# BMS029B_FETs.net
KiCad netlist of a schematic drawn in Altium Designer
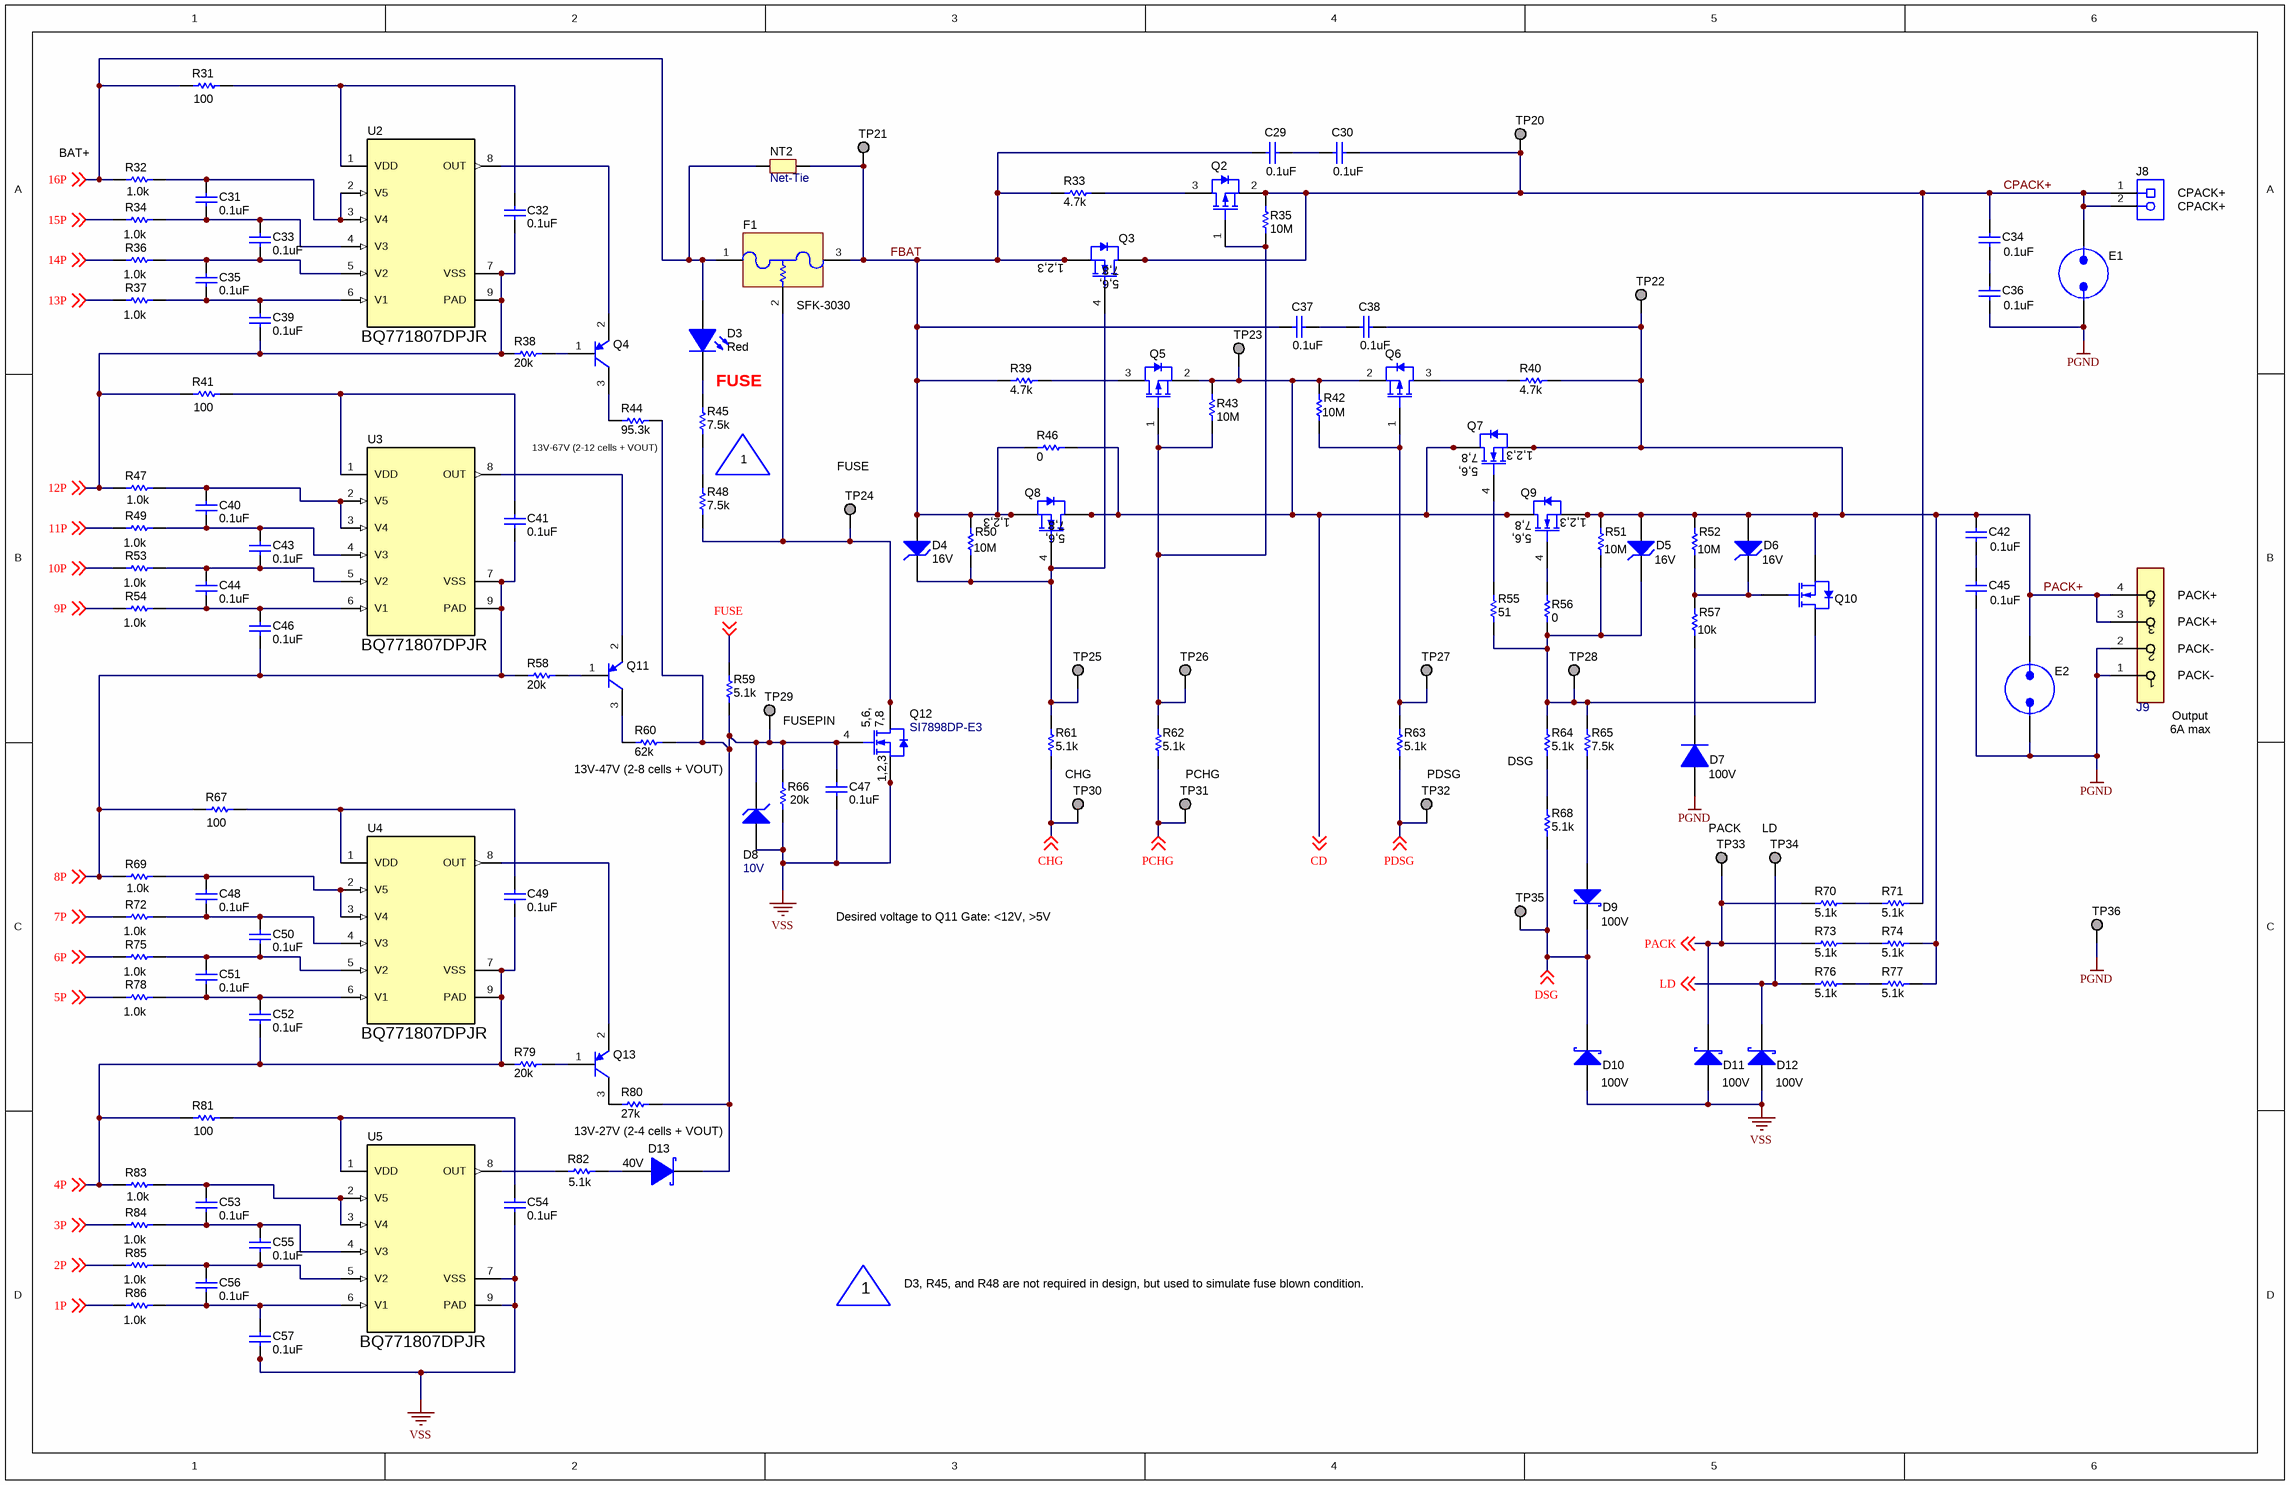
[diagram p0: BMS029B_FETs.SchDoc]

(export (version "E")
  (design (tool "Eeschema 10.0.6"))
  (components
    (comp (ref "C29")
      (value "GCJ188R72A104KA01D")
      (footprint "0603")
      (description "CAP, CERM, 0.1 uF, 100 V,+/- 10%, X7R, AEC-Q200 Grade 1, 0603")
      (fields
        (field (name "MANUFACTURER") "MuRata")
        (field (name "VALUEDISPLAYED") "0.1uF")
        (field (name "PUBLISHER") "Texas Instruments")
      )
      (libsource (lib "Altium Vault - TI") (part "Capacitor"))
    )
    (comp (ref "C30")
      (value "GCJ188R72A104KA01D")
      (footprint "0603")
      (description "CAP, CERM, 0.1 uF, 100 V,+/- 10%, X7R, AEC-Q200 Grade 1, 0603")
      (fields
        (field (name "MANUFACTURER") "MuRata")
        (field (name "VALUEDISPLAYED") "0.1uF")
        (field (name "PUBLISHER") "Texas Instruments")
      )
      (libsource (lib "Altium Vault - TI") (part "Capacitor"))
    )
    (comp (ref "C31")
      (value "885012206095")
      (footprint "0603")
      (description "CAP, CERM, 0.1 uF, 50 V, +/- 10%, X7R, 0603")
      (fields
        (field (name "VALUEDISPLAYED") "0.1uF")
        (field (name "MANUFACTURER") "Wurth Elektronik")
        (field (name "PUBLISHER") "Texas Instruments")
      )
      (libsource (lib "Altium Vault - TI") (part "Capacitor"))
    )
    (comp (ref "C32")
      (value "885012206095")
      (footprint "0603")
      (description "CAP, CERM, 0.1 uF, 50 V, +/- 10%, X7R, 0603")
      (fields
        (field (name "VALUEDISPLAYED") "0.1uF")
        (field (name "MANUFACTURER") "Wurth Elektronik")
        (field (name "PUBLISHER") "Texas Instruments")
      )
      (libsource (lib "Altium Vault - TI") (part "Capacitor"))
    )
    (comp (ref "C33")
      (value "885012206095")
      (footprint "0603")
      (description "CAP, CERM, 0.1 uF, 50 V, +/- 10%, X7R, 0603")
      (fields
        (field (name "VALUEDISPLAYED") "0.1uF")
        (field (name "MANUFACTURER") "Wurth Elektronik")
        (field (name "PUBLISHER") "Texas Instruments")
      )
      (libsource (lib "Altium Vault - TI") (part "Capacitor"))
    )
    (comp (ref "C34")
      (value "GCJ188R72A104KA01D")
      (footprint "0603")
      (description "CAP, CERM, 0.1 uF, 100 V,+/- 10%, X7R, AEC-Q200 Grade 1, 0603")
      (fields
        (field (name "MANUFACTURER") "MuRata")
        (field (name "VALUEDISPLAYED") "0.1uF")
        (field (name "PUBLISHER") "Texas Instruments")
      )
      (libsource (lib "Altium Vault - TI") (part "Capacitor"))
    )
    (comp (ref "C35")
      (value "885012206095")
      (footprint "0603")
      (description "CAP, CERM, 0.1 uF, 50 V, +/- 10%, X7R, 0603")
      (fields
        (field (name "VALUEDISPLAYED") "0.1uF")
        (field (name "MANUFACTURER") "Wurth Elektronik")
        (field (name "PUBLISHER") "Texas Instruments")
      )
      (libsource (lib "Altium Vault - TI") (part "Capacitor"))
    )
    (comp (ref "C36")
      (value "GCJ188R72A104KA01D")
      (footprint "0603")
      (description "CAP, CERM, 0.1 uF, 100 V,+/- 10%, X7R, AEC-Q200 Grade 1, 0603")
      (fields
        (field (name "MANUFACTURER") "MuRata")
        (field (name "VALUEDISPLAYED") "0.1uF")
        (field (name "PUBLISHER") "Texas Instruments")
      )
      (libsource (lib "Altium Vault - TI") (part "Capacitor"))
    )
    (comp (ref "C37")
      (value "GCJ188R72A104KA01D")
      (footprint "0603")
      (description "CAP, CERM, 0.1 uF, 100 V,+/- 10%, X7R, AEC-Q200 Grade 1, 0603")
      (fields
        (field (name "MANUFACTURER") "MuRata")
        (field (name "VALUEDISPLAYED") "0.1uF")
        (field (name "PUBLISHER") "Texas Instruments")
      )
      (libsource (lib "Altium Vault - TI") (part "Capacitor"))
    )
    (comp (ref "C38")
      (value "GCJ188R72A104KA01D")
      (footprint "0603")
      (description "CAP, CERM, 0.1 uF, 100 V,+/- 10%, X7R, AEC-Q200 Grade 1, 0603")
      (fields
        (field (name "MANUFACTURER") "MuRata")
        (field (name "VALUEDISPLAYED") "0.1uF")
        (field (name "PUBLISHER") "Texas Instruments")
      )
      (libsource (lib "Altium Vault - TI") (part "Capacitor"))
    )
    (comp (ref "C39")
      (value "885012206095")
      (footprint "0603")
      (description "CAP, CERM, 0.1 uF, 50 V, +/- 10%, X7R, 0603")
      (fields
        (field (name "VALUEDISPLAYED") "0.1uF")
        (field (name "MANUFACTURER") "Wurth Elektronik")
        (field (name "PUBLISHER") "Texas Instruments")
      )
      (libsource (lib "Altium Vault - TI") (part "Capacitor"))
    )
    (comp (ref "C40")
      (value "885012206095")
      (footprint "0603")
      (description "CAP, CERM, 0.1 uF, 50 V, +/- 10%, X7R, 0603")
      (fields
        (field (name "VALUEDISPLAYED") "0.1uF")
        (field (name "MANUFACTURER") "Wurth Elektronik")
        (field (name "PUBLISHER") "Texas Instruments")
      )
      (libsource (lib "Altium Vault - TI") (part "Capacitor"))
    )
    (comp (ref "C41")
      (value "885012206095")
      (footprint "0603")
      (description "CAP, CERM, 0.1 uF, 50 V, +/- 10%, X7R, 0603")
      (fields
        (field (name "VALUEDISPLAYED") "0.1uF")
        (field (name "MANUFACTURER") "Wurth Elektronik")
        (field (name "PUBLISHER") "Texas Instruments")
      )
      (libsource (lib "Altium Vault - TI") (part "Capacitor"))
    )
    (comp (ref "C42")
      (value "GCJ188R72A104KA01D")
      (footprint "0603")
      (description "CAP, CERM, 0.1 uF, 100 V,+/- 10%, X7R, AEC-Q200 Grade 1, 0603")
      (fields
        (field (name "MANUFACTURER") "MuRata")
        (field (name "VALUEDISPLAYED") "0.1uF")
        (field (name "PUBLISHER") "Texas Instruments")
      )
      (libsource (lib "Altium Vault - TI") (part "Capacitor"))
    )
    (comp (ref "C43")
      (value "885012206095")
      (footprint "0603")
      (description "CAP, CERM, 0.1 uF, 50 V, +/- 10%, X7R, 0603")
      (fields
        (field (name "VALUEDISPLAYED") "0.1uF")
        (field (name "MANUFACTURER") "Wurth Elektronik")
        (field (name "PUBLISHER") "Texas Instruments")
      )
      (libsource (lib "Altium Vault - TI") (part "Capacitor"))
    )
    (comp (ref "C44")
      (value "885012206095")
      (footprint "0603")
      (description "CAP, CERM, 0.1 uF, 50 V, +/- 10%, X7R, 0603")
      (fields
        (field (name "VALUEDISPLAYED") "0.1uF")
        (field (name "MANUFACTURER") "Wurth Elektronik")
        (field (name "PUBLISHER") "Texas Instruments")
      )
      (libsource (lib "Altium Vault - TI") (part "Capacitor"))
    )
    (comp (ref "C45")
      (value "GCJ188R72A104KA01D")
      (footprint "0603")
      (description "CAP, CERM, 0.1 uF, 100 V,+/- 10%, X7R, AEC-Q200 Grade 1, 0603")
      (fields
        (field (name "MANUFACTURER") "MuRata")
        (field (name "VALUEDISPLAYED") "0.1uF")
        (field (name "PUBLISHER") "Texas Instruments")
      )
      (libsource (lib "Altium Vault - TI") (part "Capacitor"))
    )
    (comp (ref "C46")
      (value "885012206095")
      (footprint "0603")
      (description "CAP, CERM, 0.1 uF, 50 V, +/- 10%, X7R, 0603")
      (fields
        (field (name "VALUEDISPLAYED") "0.1uF")
        (field (name "MANUFACTURER") "Wurth Elektronik")
        (field (name "PUBLISHER") "Texas Instruments")
      )
      (libsource (lib "Altium Vault - TI") (part "Capacitor"))
    )
    (comp (ref "C47")
      (value "885012206095")
      (footprint "0603")
      (description "CAP, CERM, 0.1 uF, 50 V, +/- 10%, X7R, 0603")
      (fields
        (field (name "VALUEDISPLAYED") "0.1uF")
        (field (name "MANUFACTURER") "Wurth Elektronik")
        (field (name "PUBLISHER") "Texas Instruments")
      )
      (libsource (lib "Altium Vault - TI") (part "Capacitor"))
    )
    (comp (ref "C48")
      (value "885012206095")
      (footprint "0603")
      (description "CAP, CERM, 0.1 uF, 50 V, +/- 10%, X7R, 0603")
      (fields
        (field (name "VALUEDISPLAYED") "0.1uF")
        (field (name "MANUFACTURER") "Wurth Elektronik")
        (field (name "PUBLISHER") "Texas Instruments")
      )
      (libsource (lib "Altium Vault - TI") (part "Capacitor"))
    )
    (comp (ref "C49")
      (value "885012206095")
      (footprint "0603")
      (description "CAP, CERM, 0.1 uF, 50 V, +/- 10%, X7R, 0603")
      (fields
        (field (name "VALUEDISPLAYED") "0.1uF")
        (field (name "MANUFACTURER") "Wurth Elektronik")
        (field (name "PUBLISHER") "Texas Instruments")
      )
      (libsource (lib "Altium Vault - TI") (part "Capacitor"))
    )
    (comp (ref "C50")
      (value "885012206095")
      (footprint "0603")
      (description "CAP, CERM, 0.1 uF, 50 V, +/- 10%, X7R, 0603")
      (fields
        (field (name "VALUEDISPLAYED") "0.1uF")
        (field (name "MANUFACTURER") "Wurth Elektronik")
        (field (name "PUBLISHER") "Texas Instruments")
      )
      (libsource (lib "Altium Vault - TI") (part "Capacitor"))
    )
    (comp (ref "C51")
      (value "885012206095")
      (footprint "0603")
      (description "CAP, CERM, 0.1 uF, 50 V, +/- 10%, X7R, 0603")
      (fields
        (field (name "VALUEDISPLAYED") "0.1uF")
        (field (name "MANUFACTURER") "Wurth Elektronik")
        (field (name "PUBLISHER") "Texas Instruments")
      )
      (libsource (lib "Altium Vault - TI") (part "Capacitor"))
    )
    (comp (ref "C52")
      (value "885012206095")
      (footprint "0603")
      (description "CAP, CERM, 0.1 uF, 50 V, +/- 10%, X7R, 0603")
      (fields
        (field (name "VALUEDISPLAYED") "0.1uF")
        (field (name "MANUFACTURER") "Wurth Elektronik")
        (field (name "PUBLISHER") "Texas Instruments")
      )
      (libsource (lib "Altium Vault - TI") (part "Capacitor"))
    )
    (comp (ref "C53")
      (value "885012206095")
      (footprint "0603")
      (description "CAP, CERM, 0.1 uF, 50 V, +/- 10%, X7R, 0603")
      (fields
        (field (name "VALUEDISPLAYED") "0.1uF")
        (field (name "MANUFACTURER") "Wurth Elektronik")
        (field (name "PUBLISHER") "Texas Instruments")
      )
      (libsource (lib "Altium Vault - TI") (part "Capacitor"))
    )
    (comp (ref "C54")
      (value "885012206095")
      (footprint "0603")
      (description "CAP, CERM, 0.1 uF, 50 V, +/- 10%, X7R, 0603")
      (fields
        (field (name "VALUEDISPLAYED") "0.1uF")
        (field (name "MANUFACTURER") "Wurth Elektronik")
        (field (name "PUBLISHER") "Texas Instruments")
      )
      (libsource (lib "Altium Vault - TI") (part "Capacitor"))
    )
    (comp (ref "C55")
      (value "885012206095")
      (footprint "0603")
      (description "CAP, CERM, 0.1 uF, 50 V, +/- 10%, X7R, 0603")
      (fields
        (field (name "VALUEDISPLAYED") "0.1uF")
        (field (name "MANUFACTURER") "Wurth Elektronik")
        (field (name "PUBLISHER") "Texas Instruments")
      )
      (libsource (lib "Altium Vault - TI") (part "Capacitor"))
    )
    (comp (ref "C56")
      (value "885012206095")
      (footprint "0603")
      (description "CAP, CERM, 0.1 uF, 50 V, +/- 10%, X7R, 0603")
      (fields
        (field (name "VALUEDISPLAYED") "0.1uF")
        (field (name "MANUFACTURER") "Wurth Elektronik")
        (field (name "PUBLISHER") "Texas Instruments")
      )
      (libsource (lib "Altium Vault - TI") (part "Capacitor"))
    )
    (comp (ref "C57")
      (value "885012206095")
      (footprint "0603")
      (description "CAP, CERM, 0.1 uF, 50 V, +/- 10%, X7R, 0603")
      (fields
        (field (name "VALUEDISPLAYED") "0.1uF")
        (field (name "MANUFACTURER") "Wurth Elektronik")
        (field (name "PUBLISHER") "Texas Instruments")
      )
      (libsource (lib "Altium Vault - TI") (part "Capacitor"))
    )
    (comp (ref "D3")
      (value "Red")
      (footprint "WL-SMCW_RED")
      (description "LED, Red, SMD")
      (fields (field (name "MANUFACTURER") "Wurth Elektronik") (field (name "PARTNUMBER") "150060RS75000"))
      (libsource (lib "Altium Vault - TI") (part "CMP-0002947-3"))
    )
    (comp (ref "D4")
      (value "16V")
      (footprint "SOD-123")
      (description "Diode, Zener, 16 V, 500 mW, SOD-123")
      (fields (field (name "MANUFACTURER") "Diodes Inc.") (field (name "PARTNUMBER") "MMSZ5246B-7-F"))
      (libsource (lib "Altium Vault - TI") (part "Zener"))
    )
    (comp (ref "D5")
      (value "16V")
      (footprint "SOD-123")
      (description "Diode, Zener, 16 V, 500 mW, SOD-123")
      (fields (field (name "PARTNUMBER") "MMSZ5246B-7-F") (field (name "MANUFACTURER") "Diodes Inc."))
      (libsource (lib "Altium Vault - TI") (part "CMP-0005754-4"))
    )
    (comp (ref "D6")
      (value "16V")
      (footprint "SOD-123")
      (description "Diode, Zener, 16 V, 500 mW, SOD-123")
      (fields (field (name "PARTNUMBER") "MMSZ5246B-7-F") (field (name "MANUFACTURER") "Diodes Inc."))
      (libsource (lib "Altium Vault - TI") (part "CMP-0005754-4"))
    )
    (comp (ref "D7")
      (value "100V")
      (footprint "SOD-123")
      (description "Diode, Ultrafast, 100 V, 0.15 A, SOD-123")
      (fields (field (name "PARTNUMBER") "1N4148W-7-F") (field (name "MANUFACTURER") "Diodes Inc."))
      (libsource (lib "Altium Vault - TI") (part "CMP-0029001-2"))
    )
    (comp (ref "D8")
      (value "10V")
      (footprint "SOD-123")
      (description "Diode, Zener, 10 V, 500 mW, SOD-123")
      (fields (field (name "MANUFACTURER") "ON Semiconductor") (field (name "PARTNUMBER") "MMSZ4697T1G"))
      (libsource (lib "Altium Vault - TI") (part "Zener"))
    )
    (comp (ref "D9")
      (value "100V")
      (footprint "SOD-123")
      (description "Diode, Schottky, 100 V, 0.15 A, SOD-123")
      (fields (field (name "MANUFACTURER") "Diodes Inc.") (field (name "PARTNUMBER") "BAT46W-7-F"))
      (libsource (lib "Altium Vault - TI") (part "DIODE_SCHOTTKY"))
    )
    (comp (ref "D10")
      (value "100V")
      (footprint "SOD-123")
      (description "Diode, Schottky, 100 V, 0.15 A, SOD-123")
      (fields (field (name "MANUFACTURER") "Diodes Inc.") (field (name "PARTNUMBER") "BAT46W-7-F"))
      (libsource (lib "Altium Vault - TI") (part "DIODE_SCHOTTKY"))
    )
    (comp (ref "D11")
      (value "100V")
      (footprint "SOD-123")
      (description "Diode, Schottky, 100 V, 0.15 A, SOD-123")
      (fields (field (name "MANUFACTURER") "Diodes Inc.") (field (name "PARTNUMBER") "BAT46W-7-F"))
      (libsource (lib "Altium Vault - TI") (part "DIODE_SCHOTTKY"))
    )
    (comp (ref "D12")
      (value "100V")
      (footprint "SOD-123")
      (description "Diode, Schottky, 100 V, 0.15 A, SOD-123")
      (fields (field (name "MANUFACTURER") "Diodes Inc.") (field (name "PARTNUMBER") "BAT46W-7-F"))
      (libsource (lib "Altium Vault - TI") (part "DIODE_SCHOTTKY"))
    )
    (comp (ref "D13")
      (value "40V")
      (footprint "SOT-323")
      (description "Diode, Schottky, 40 V, 0.2 A, SOT-323")
      (fields (field (name "PARTNUMBER") "BAS40W-7-F") (field (name "MANUFACTURER") "Diodes Inc."))
      (libsource (lib "Altium Vault - TI") (part "CMP-0028438-2"))
    )
    (comp (ref "E1")
      (value "Spark Gap")
      (footprint "SPARK_GAP2")
      (libsource (lib "Altium Vault - TI") (part "CMP-0079939-1"))
    )
    (comp (ref "E2")
      (value "Spark Gap")
      (footprint "SPARK_GAP2")
      (libsource (lib "Altium Vault - TI") (part "CMP-0079939-1"))
    )
    (comp (ref "F1")
      (value "SFK-3030")
      (footprint "FUSE_SFK-xx30x")
      (description "Fuse, 30 A, 62 VDC, SMD")
      (fields (field (name "MANUFACTURER") "Dexerials Corporation"))
      (libsource (lib "Altium Vault - TI") (part "FUSE_SFK-XX30X"))
    )
    (comp (ref "J8")
      (value "ED555/2DS")
      (footprint "TERM_BLK_ED555-2DS")
      (description "Terminal Block, 3.5mm Pitch, 2x1, TH")
      (fields
        (field (name "MANUFACTURER") "On-Shore Technology")
        (field (name "PUBLISHER") "Texas Instruments")
      )
      (libsource (lib "Altium Vault - TI") (part "CMP-0074913-1"))
    )
    (comp (ref "J9")
      (value "OSTTE040161")
      (footprint "FP-OSTTE040161_HDR4-MFG")
      (description "TERM BLOCK 3.5MM VERT 4POS PCB")
      (fields (field (name "MANUFACTURER") "On Shore Technology"))
      (libsource (lib "Altium Vault - TI") (part "SYM-OSTTE040161"))
    )
    (comp (ref "NT2")
      (value "Net-Tie")
      (footprint "Net-Tie_50milWide_30milLong")
      (description "Single point connection between nets.")
      (libsource (lib "Altium Vault - TI") (part "Net-Tie"))
    )
    (comp (ref "Q2")
      (value "SI2325DS-T1-E3")
      (footprint "SOT-23")
      (description "MOSFET, P-CH, -150 V, -0.53 A, SOT-23")
      (fields (field (name "MANUFACTURER") "Vishay-Siliconix"))
      (libsource (lib "Altium Vault - TI") (part "MOSFET_P_D3G1S2"))
    )
    (comp (ref "Q3")
      (value "BSZ900N15NS3 G")
      (footprint "PG-TSDSON-8")
      (description "MOSFET, N-CH, 150 V, 13 A, PG-TSDSON-8")
      (fields
        (field (name "MANUFACTURER") "Infineon Technologies")
        (field (name "PUBLISHER") "Texas Instruments")
      )
      (libsource (lib "Altium Vault - TI") (part "MOSFET_N_D56789G4S123"))
    )
    (comp (ref "Q4")
      (value "MMBT5401LT1G")
      (footprint "SOT-23")
      (description "Transistor, PNP, 150 V, 0.5 A, SOT-23")
      (fields (field (name "MANUFACTURER") "ON Semiconductor") (field (name "PUBLISHER") "Texas Instruments"))
      (libsource (lib "Altium Vault - TI") (part "BJT_PNP_C3B1E2"))
    )
    (comp (ref "Q5")
      (value "SI2325DS-T1-E3")
      (footprint "SOT-23")
      (description "MOSFET, P-CH, -150 V, -0.53 A, SOT-23")
      (fields (field (name "MANUFACTURER") "Vishay-Siliconix"))
      (libsource (lib "Altium Vault - TI") (part "MOSFET_P_D3G1S2"))
    )
    (comp (ref "Q6")
      (value "SI2325DS-T1-E3")
      (footprint "SOT-23")
      (description "MOSFET, P-CH, -150 V, -0.53 A, SOT-23")
      (fields (field (name "MANUFACTURER") "Vishay-Siliconix"))
      (libsource (lib "Altium Vault - TI") (part "MOSFET_P_D3G1S2"))
    )
    (comp (ref "Q7")
      (value "BSC160N15NS5ATMA1")
      (footprint "PG-TDSON-8")
      (description "MOSFET, N-CH, 150 V, 56 A, PG-TDSON-8")
      (fields
        (field (name "MANUFACTURER") "Infineon Technologies")
        (field (name "PUBLISHER") "Texas Instruments")
      )
      (libsource (lib "Altium Vault - TI") (part "MOSFET_N_D56789G4S123"))
    )
    (comp (ref "Q8")
      (value "BSC160N15NS5ATMA1")
      (footprint "PG-TDSON-8")
      (description "MOSFET, N-CH, 150 V, 56 A, PG-TDSON-8")
      (fields
        (field (name "MANUFACTURER") "Infineon Technologies")
        (field (name "PUBLISHER") "Texas Instruments")
      )
      (libsource (lib "Altium Vault - TI") (part "MOSFET_N_D56789G4S123"))
    )
    (comp (ref "Q9")
      (value "BSC160N15NS5ATMA1")
      (footprint "PG-TDSON-8")
      (description "MOSFET, N-CH, 150 V, 56 A, PG-TDSON-8")
      (fields
        (field (name "MANUFACTURER") "Infineon Technologies")
        (field (name "PUBLISHER") "Texas Instruments")
      )
      (libsource (lib "Altium Vault - TI") (part "MOSFET_N_D56789G4S123"))
    )
    (comp (ref "Q10")
      (value "MOSFET_N_D3G1S2")
      (footprint "SOT-323")
      (description "MOSFET, N-CH, 60 V, 0.31 A, SOT-323")
      (fields
        (field (name "PARTNUMBER") "2N7002KW")
        (field (name "MANUFACTURER") "Fairchild Semiconductor")
        (field (name "PUBLISHER") "Texas Instruments")
      )
      (libsource (lib "Altium Vault - TI") (part "CMP-0000774-1"))
    )
    (comp (ref "Q11")
      (value "MMBT5401LT1G")
      (footprint "SOT-23")
      (description "Transistor, PNP, 150 V, 0.5 A, SOT-23")
      (fields (field (name "MANUFACTURER") "ON Semiconductor") (field (name "PUBLISHER") "Texas Instruments"))
      (libsource (lib "Altium Vault - TI") (part "BJT_PNP_C3B1E2"))
    )
    (comp (ref "Q12")
      (value "SI7898DP-E3")
      (footprint "PowerPAK_SO-8")
      (description "MOSFET, N-CH, 150 V, 3 A, PowerPAK SO-8")
      (fields (field (name "MANUFACTURER") "Vishay-Siliconix") (field (name "PUBLISHER") "Texas Instruments"))
      (libsource (lib "Altium Vault - TI") (part "MOSFET_N_D56789G4S123"))
    )
    (comp (ref "Q13")
      (value "MMBT5401LT1G")
      (footprint "SOT-23")
      (description "Transistor, PNP, 150 V, 0.5 A, SOT-23")
      (fields (field (name "MANUFACTURER") "ON Semiconductor") (field (name "PUBLISHER") "Texas Instruments"))
      (libsource (lib "Altium Vault - TI") (part "BJT_PNP_C3B1E2"))
    )
    (comp (ref "R31")
      (value "Resistor")
      (footprint "0603")
      (description "RES, 100, 5%, 0.1 W, AEC-Q200 Grade 0, 0603")
      (fields
        (field (name "PARTNUMBER") "CRCW0603100RJNEA")
        (field (name "MANUFACTURER") "Vishay-Dale")
        (field (name "VALUEDISPLAYED") "100")
        (field (name "PUBLISHER") "Texas Instruments")
      )
      (libsource (lib "Altium Vault - TI") (part "Resistor"))
    )
    (comp (ref "R32")
      (value "Resistor")
      (footprint "0603")
      (description "RES, 1.0 k, 5%, 0.1 W, AEC-Q200 Grade 0, 0603")
      (fields
        (field (name "PARTNUMBER") "CRCW06031K00JNEA")
        (field (name "MANUFACTURER") "Vishay-Dale")
        (field (name "VALUEDISPLAYED") "1.0k")
        (field (name "PUBLISHER") "Texas Instruments")
      )
      (libsource (lib "Altium Vault - TI") (part "Resistor"))
    )
    (comp (ref "R33")
      (value "CRCW25124K70JNEG")
      (footprint "2512")
      (description "RES, 4.7 k, 5%, 1 W, AEC-Q200 Grade 0, 2512")
      (fields (field (name "MANUFACTURER") "Vishay-Dale") (field (name "VALUEDISPLAYED") "4.7k"))
      (libsource (lib "Altium Vault - TI") (part "Resistor"))
    )
    (comp (ref "R34")
      (value "Resistor")
      (footprint "0603")
      (description "RES, 1.0 k, 5%, 0.1 W, AEC-Q200 Grade 0, 0603")
      (fields
        (field (name "PARTNUMBER") "CRCW06031K00JNEA")
        (field (name "MANUFACTURER") "Vishay-Dale")
        (field (name "VALUEDISPLAYED") "1.0k")
        (field (name "PUBLISHER") "Texas Instruments")
      )
      (libsource (lib "Altium Vault - TI") (part "Resistor"))
    )
    (comp (ref "R35")
      (value "Resistor")
      (footprint "0603")
      (description "RES, 10 M, 5%, 0.1 W, AEC-Q200 Grade 0, 0603")
      (fields
        (field (name "PARTNUMBER") "CRCW060310M0JNEA")
        (field (name "MANUFACTURER") "Vishay-Dale")
        (field (name "VALUEDISPLAYED") "10M")
        (field (name "PUBLISHER") "Texas Instruments")
      )
      (libsource (lib "Altium Vault - TI") (part "Resistor"))
    )
    (comp (ref "R36")
      (value "Resistor")
      (footprint "0603")
      (description "RES, 1.0 k, 5%, 0.1 W, AEC-Q200 Grade 0, 0603")
      (fields
        (field (name "PARTNUMBER") "CRCW06031K00JNEA")
        (field (name "MANUFACTURER") "Vishay-Dale")
        (field (name "VALUEDISPLAYED") "1.0k")
        (field (name "PUBLISHER") "Texas Instruments")
      )
      (libsource (lib "Altium Vault - TI") (part "Resistor"))
    )
    (comp (ref "R37")
      (value "Resistor")
      (footprint "0603")
      (description "RES, 1.0 k, 5%, 0.1 W, AEC-Q200 Grade 0, 0603")
      (fields
        (field (name "PARTNUMBER") "CRCW06031K00JNEA")
        (field (name "MANUFACTURER") "Vishay-Dale")
        (field (name "VALUEDISPLAYED") "1.0k")
        (field (name "PUBLISHER") "Texas Instruments")
      )
      (libsource (lib "Altium Vault - TI") (part "Resistor"))
    )
    (comp (ref "R38")
      (value "CRCW060320K0JNEA")
      (footprint "0603")
      (description "RES, 20 k, 5%, 0.1 W, AEC-Q200 Grade 0, 0603")
      (fields (field (name "MANUFACTURER") "Vishay-Dale") (field (name "VALUEDISPLAYED") "20k"))
      (libsource (lib "Altium Vault - TI") (part "Resistor"))
    )
    (comp (ref "R39")
      (value "CRCW25124K70JNEG")
      (footprint "2512")
      (description "RES, 4.7 k, 5%, 1 W, AEC-Q200 Grade 0, 2512")
      (fields (field (name "MANUFACTURER") "Vishay-Dale") (field (name "VALUEDISPLAYED") "4.7k"))
      (libsource (lib "Altium Vault - TI") (part "Resistor"))
    )
    (comp (ref "R40")
      (value "CRCW25124K70JNEG")
      (footprint "2512")
      (description "RES, 4.7 k, 5%, 1 W, AEC-Q200 Grade 0, 2512")
      (fields (field (name "MANUFACTURER") "Vishay-Dale") (field (name "VALUEDISPLAYED") "4.7k"))
      (libsource (lib "Altium Vault - TI") (part "Resistor"))
    )
    (comp (ref "R41")
      (value "Resistor")
      (footprint "0603")
      (description "RES, 100, 5%, 0.1 W, AEC-Q200 Grade 0, 0603")
      (fields
        (field (name "PARTNUMBER") "CRCW0603100RJNEA")
        (field (name "MANUFACTURER") "Vishay-Dale")
        (field (name "VALUEDISPLAYED") "100")
        (field (name "PUBLISHER") "Texas Instruments")
      )
      (libsource (lib "Altium Vault - TI") (part "Resistor"))
    )
    (comp (ref "R42")
      (value "Resistor")
      (footprint "0603")
      (description "RES, 10 M, 5%, 0.1 W, AEC-Q200 Grade 0, 0603")
      (fields
        (field (name "PARTNUMBER") "CRCW060310M0JNEA")
        (field (name "MANUFACTURER") "Vishay-Dale")
        (field (name "VALUEDISPLAYED") "10M")
        (field (name "PUBLISHER") "Texas Instruments")
      )
      (libsource (lib "Altium Vault - TI") (part "Resistor"))
    )
    (comp (ref "R43")
      (value "Resistor")
      (footprint "0603")
      (description "RES, 10 M, 5%, 0.1 W, AEC-Q200 Grade 0, 0603")
      (fields
        (field (name "PARTNUMBER") "CRCW060310M0JNEA")
        (field (name "MANUFACTURER") "Vishay-Dale")
        (field (name "VALUEDISPLAYED") "10M")
        (field (name "PUBLISHER") "Texas Instruments")
      )
      (libsource (lib "Altium Vault - TI") (part "Resistor"))
    )
    (comp (ref "R44")
      (value "RC0603FR-0795K3L")
      (footprint "0603")
      (description "RES, 95.3 k, 1%, 0.1 W, 0603")
      (fields (field (name "MANUFACTURER") "Yageo") (field (name "VALUEDISPLAYED") "95.3k"))
      (libsource (lib "Altium Vault - TI") (part "Resistor"))
    )
    (comp (ref "R45")
      (value "CRCW12067K50JNEA")
      (footprint "1206")
      (description "RES, 7.5 k, 5%, 0.25 W, AEC-Q200 Grade 0, 1206")
      (fields (field (name "MANUFACTURER") "Vishay-Dale") (field (name "VALUEDISPLAYED") "7.5k"))
      (libsource (lib "Altium Vault - TI") (part "Resistor"))
    )
    (comp (ref "R46")
      (value "Resistor")
      (footprint "2512_WIDE_VISHAY")
      (description "RES, 0, 5%, 2 W, 2512 WIDE")
      (fields
        (field (name "PARTNUMBER") "RCL12250000Z0EG")
        (field (name "VALUEDISPLAYED") "0")
        (field (name "MANUFACTURER") "Vishay Draloric")
        (field (name "PUBLISHER") "Texas Instruments")
      )
      (libsource (lib "Altium Vault - TI") (part "Resistor"))
    )
    (comp (ref "R47")
      (value "Resistor")
      (footprint "0603")
      (description "RES, 1.0 k, 5%, 0.1 W, AEC-Q200 Grade 0, 0603")
      (fields
        (field (name "PARTNUMBER") "CRCW06031K00JNEA")
        (field (name "MANUFACTURER") "Vishay-Dale")
        (field (name "VALUEDISPLAYED") "1.0k")
        (field (name "PUBLISHER") "Texas Instruments")
      )
      (libsource (lib "Altium Vault - TI") (part "Resistor"))
    )
    (comp (ref "R48")
      (value "CRCW12067K50JNEA")
      (footprint "1206")
      (description "RES, 7.5 k, 5%, 0.25 W, AEC-Q200 Grade 0, 1206")
      (fields (field (name "MANUFACTURER") "Vishay-Dale") (field (name "VALUEDISPLAYED") "7.5k"))
      (libsource (lib "Altium Vault - TI") (part "Resistor"))
    )
    (comp (ref "R49")
      (value "Resistor")
      (footprint "0603")
      (description "RES, 1.0 k, 5%, 0.1 W, AEC-Q200 Grade 0, 0603")
      (fields
        (field (name "PARTNUMBER") "CRCW06031K00JNEA")
        (field (name "MANUFACTURER") "Vishay-Dale")
        (field (name "VALUEDISPLAYED") "1.0k")
        (field (name "PUBLISHER") "Texas Instruments")
      )
      (libsource (lib "Altium Vault - TI") (part "Resistor"))
    )
    (comp (ref "R50")
      (value "Resistor")
      (footprint "0603")
      (description "RES, 10 M, 5%, 0.1 W, AEC-Q200 Grade 0, 0603")
      (fields
        (field (name "PARTNUMBER") "CRCW060310M0JNEA")
        (field (name "MANUFACTURER") "Vishay-Dale")
        (field (name "VALUEDISPLAYED") "10M")
        (field (name "PUBLISHER") "Texas Instruments")
      )
      (libsource (lib "Altium Vault - TI") (part "Resistor"))
    )
    (comp (ref "R51")
      (value "Resistor")
      (footprint "0603")
      (description "RES, 10 M, 5%, 0.1 W, AEC-Q200 Grade 0, 0603")
      (fields
        (field (name "PARTNUMBER") "CRCW060310M0JNEA")
        (field (name "MANUFACTURER") "Vishay-Dale")
        (field (name "VALUEDISPLAYED") "10M")
        (field (name "PUBLISHER") "Texas Instruments")
      )
      (libsource (lib "Altium Vault - TI") (part "Resistor"))
    )
    (comp (ref "R52")
      (value "Resistor")
      (footprint "0603")
      (description "RES, 10 M, 5%, 0.1 W, AEC-Q200 Grade 0, 0603")
      (fields
        (field (name "PARTNUMBER") "CRCW060310M0JNEA")
        (field (name "MANUFACTURER") "Vishay-Dale")
        (field (name "VALUEDISPLAYED") "10M")
        (field (name "PUBLISHER") "Texas Instruments")
      )
      (libsource (lib "Altium Vault - TI") (part "Resistor"))
    )
    (comp (ref "R53")
      (value "Resistor")
      (footprint "0603")
      (description "RES, 1.0 k, 5%, 0.1 W, AEC-Q200 Grade 0, 0603")
      (fields
        (field (name "PARTNUMBER") "CRCW06031K00JNEA")
        (field (name "MANUFACTURER") "Vishay-Dale")
        (field (name "VALUEDISPLAYED") "1.0k")
        (field (name "PUBLISHER") "Texas Instruments")
      )
      (libsource (lib "Altium Vault - TI") (part "Resistor"))
    )
    (comp (ref "R54")
      (value "Resistor")
      (footprint "0603")
      (description "RES, 1.0 k, 5%, 0.1 W, AEC-Q200 Grade 0, 0603")
      (fields
        (field (name "PARTNUMBER") "CRCW06031K00JNEA")
        (field (name "MANUFACTURER") "Vishay-Dale")
        (field (name "VALUEDISPLAYED") "1.0k")
        (field (name "PUBLISHER") "Texas Instruments")
      )
      (libsource (lib "Altium Vault - TI") (part "Resistor"))
    )
    (comp (ref "R55")
      (value "CRCW060351R0JNEA")
      (footprint "0603")
      (description "RES, 51, 5%, 0.1 W, AEC-Q200 Grade 0, 0603")
      (fields (field (name "MANUFACTURER") "Vishay-Dale") (field (name "VALUEDISPLAYED") "51"))
      (libsource (lib "Altium Vault - TI") (part "Resistor"))
    )
    (comp (ref "R56")
      (value "CRCW06030000Z0EA")
      (footprint "0603")
      (description "RES, 0, 5%, 0.1 W, AEC-Q200 Grade 0, 0603")
      (fields (field (name "MANUFACTURER") "Vishay-Dale") (field (name "VALUEDISPLAYED") "0"))
      (libsource (lib "Altium Vault - TI") (part "Resistor"))
    )
    (comp (ref "R57")
      (value "Resistor")
      (footprint "0603")
      (description "RES, 10 k, 5%, 0.1 W, AEC-Q200 Grade 0, 0603")
      (fields
        (field (name "PARTNUMBER") "CRCW060310K0JNEA")
        (field (name "MANUFACTURER") "Vishay-Dale")
        (field (name "VALUEDISPLAYED") "10k")
        (field (name "PUBLISHER") "Texas Instruments")
      )
      (libsource (lib "Altium Vault - TI") (part "Resistor"))
    )
    (comp (ref "R58")
      (value "CRCW060320K0JNEA")
      (footprint "0603")
      (description "RES, 20 k, 5%, 0.1 W, AEC-Q200 Grade 0, 0603")
      (fields (field (name "MANUFACTURER") "Vishay-Dale") (field (name "VALUEDISPLAYED") "20k"))
      (libsource (lib "Altium Vault - TI") (part "Resistor"))
    )
    (comp (ref "R59")
      (value "Resistor")
      (footprint "0603")
      (description "RES, 5.1 k, 5%, 0.1 W, AEC-Q200 Grade 0, 0603")
      (fields
        (field (name "PARTNUMBER") "CRCW06035K10JNEA")
        (field (name "MANUFACTURER") "Vishay-Dale")
        (field (name "VALUEDISPLAYED") "5.1k")
        (field (name "PUBLISHER") "Texas Instruments")
      )
      (libsource (lib "Altium Vault - TI") (part "Resistor"))
    )
    (comp (ref "R60")
      (value "RC0603JR-0762KL")
      (footprint "0603")
      (description "RES, 62 k, 5%, 0.1 W, 0603")
      (fields (field (name "MANUFACTURER") "Yageo") (field (name "VALUEDISPLAYED") "62k"))
      (libsource (lib "Altium Vault - TI") (part "Resistor"))
    )
    (comp (ref "R61")
      (value "CRCW06035K10JNEA")
      (footprint "0603")
      (description "RES, 5.1 k, 5%, 0.1 W, AEC-Q200 Grade 0, 0603")
      (fields (field (name "VALUEDISPLAYED") "5.1k") (field (name "MANUFACTURER") "Vishay-Dale"))
      (libsource (lib "Altium Vault - TI") (part "Resistor"))
    )
    (comp (ref "R62")
      (value "CRCW06035K10JNEA")
      (footprint "0603")
      (description "RES, 5.1 k, 5%, 0.1 W, AEC-Q200 Grade 0, 0603")
      (fields (field (name "VALUEDISPLAYED") "5.1k") (field (name "MANUFACTURER") "Vishay-Dale"))
      (libsource (lib "Altium Vault - TI") (part "Resistor"))
    )
    (comp (ref "R63")
      (value "CRCW06035K10JNEA")
      (footprint "0603")
      (description "RES, 5.1 k, 5%, 0.1 W, AEC-Q200 Grade 0, 0603")
      (fields (field (name "VALUEDISPLAYED") "5.1k") (field (name "MANUFACTURER") "Vishay-Dale"))
      (libsource (lib "Altium Vault - TI") (part "Resistor"))
    )
    (comp (ref "R64")
      (value "CRCW12065K10JNEA")
      (footprint "1206")
      (description "RES, 5.1 k, 5%, 0.25 W, AEC-Q200 Grade 0, 1206")
      (fields (field (name "VALUEDISPLAYED") "5.1k") (field (name "MANUFACTURER") "Vishay-Dale"))
      (libsource (lib "Altium Vault - TI") (part "Resistor"))
    )
    (comp (ref "R65")
      (value "CRCW06037K50JNEA")
      (footprint "0603")
      (description "RES, 7.5 k, 5%, 0.1 W, AEC-Q200 Grade 0, 0603")
      (fields (field (name "MANUFACTURER") "Vishay-Dale") (field (name "VALUEDISPLAYED") "7.5k"))
      (libsource (lib "Altium Vault - TI") (part "Resistor"))
    )
    (comp (ref "R66")
      (value "Resistor")
      (footprint "0603")
      (description "RES, 20 k, 5%, 0.1 W, AEC-Q200 Grade 0, 0603")
      (fields
        (field (name "PARTNUMBER") "CRCW060320K0JNEA")
        (field (name "MANUFACTURER") "Vishay-Dale")
        (field (name "VALUEDISPLAYED") "20k")
        (field (name "PUBLISHER") "Texas Instruments")
      )
      (libsource (lib "Altium Vault - TI") (part "Resistor"))
    )
    (comp (ref "R67")
      (value "Resistor")
      (footprint "0603")
      (description "RES, 100, 5%, 0.1 W, AEC-Q200 Grade 0, 0603")
      (fields
        (field (name "PARTNUMBER") "CRCW0603100RJNEA")
        (field (name "MANUFACTURER") "Vishay-Dale")
        (field (name "VALUEDISPLAYED") "100")
        (field (name "PUBLISHER") "Texas Instruments")
      )
      (libsource (lib "Altium Vault - TI") (part "Resistor"))
    )
    (comp (ref "R68")
      (value "CRCW12065K10JNEA")
      (footprint "1206")
      (description "RES, 5.1 k, 5%, 0.25 W, AEC-Q200 Grade 0, 1206")
      (fields (field (name "VALUEDISPLAYED") "5.1k") (field (name "MANUFACTURER") "Vishay-Dale"))
      (libsource (lib "Altium Vault - TI") (part "Resistor"))
    )
    (comp (ref "R69")
      (value "Resistor")
      (footprint "0603")
      (description "RES, 1.0 k, 5%, 0.1 W, AEC-Q200 Grade 0, 0603")
      (fields
        (field (name "PARTNUMBER") "CRCW06031K00JNEA")
        (field (name "MANUFACTURER") "Vishay-Dale")
        (field (name "VALUEDISPLAYED") "1.0k")
        (field (name "PUBLISHER") "Texas Instruments")
      )
      (libsource (lib "Altium Vault - TI") (part "Resistor"))
    )
    (comp (ref "R70")
      (value "CRCW12065K10JNEA")
      (footprint "1206")
      (description "RES, 5.1 k, 5%, 0.25 W, AEC-Q200 Grade 0, 1206")
      (fields (field (name "VALUEDISPLAYED") "5.1k") (field (name "MANUFACTURER") "Vishay-Dale"))
      (libsource (lib "Altium Vault - TI") (part "Resistor"))
    )
    (comp (ref "R71")
      (value "CRCW12065K10JNEA")
      (footprint "1206")
      (description "RES, 5.1 k, 5%, 0.25 W, AEC-Q200 Grade 0, 1206")
      (fields (field (name "VALUEDISPLAYED") "5.1k") (field (name "MANUFACTURER") "Vishay-Dale"))
      (libsource (lib "Altium Vault - TI") (part "Resistor"))
    )
    (comp (ref "R72")
      (value "Resistor")
      (footprint "0603")
      (description "RES, 1.0 k, 5%, 0.1 W, AEC-Q200 Grade 0, 0603")
      (fields
        (field (name "PARTNUMBER") "CRCW06031K00JNEA")
        (field (name "MANUFACTURER") "Vishay-Dale")
        (field (name "VALUEDISPLAYED") "1.0k")
        (field (name "PUBLISHER") "Texas Instruments")
      )
      (libsource (lib "Altium Vault - TI") (part "Resistor"))
    )
    (comp (ref "R73")
      (value "CRCW12065K10JNEA")
      (footprint "1206")
      (description "RES, 5.1 k, 5%, 0.25 W, AEC-Q200 Grade 0, 1206")
      (fields (field (name "VALUEDISPLAYED") "5.1k") (field (name "MANUFACTURER") "Vishay-Dale"))
      (libsource (lib "Altium Vault - TI") (part "Resistor"))
    )
    (comp (ref "R74")
      (value "CRCW12065K10JNEA")
      (footprint "1206")
      (description "RES, 5.1 k, 5%, 0.25 W, AEC-Q200 Grade 0, 1206")
      (fields (field (name "VALUEDISPLAYED") "5.1k") (field (name "MANUFACTURER") "Vishay-Dale"))
      (libsource (lib "Altium Vault - TI") (part "Resistor"))
    )
    (comp (ref "R75")
      (value "Resistor")
      (footprint "0603")
      (description "RES, 1.0 k, 5%, 0.1 W, AEC-Q200 Grade 0, 0603")
      (fields
        (field (name "PARTNUMBER") "CRCW06031K00JNEA")
        (field (name "MANUFACTURER") "Vishay-Dale")
        (field (name "VALUEDISPLAYED") "1.0k")
        (field (name "PUBLISHER") "Texas Instruments")
      )
      (libsource (lib "Altium Vault - TI") (part "Resistor"))
    )
    (comp (ref "R76")
      (value "CRCW12065K10JNEA")
      (footprint "1206")
      (description "RES, 5.1 k, 5%, 0.25 W, AEC-Q200 Grade 0, 1206")
      (fields (field (name "VALUEDISPLAYED") "5.1k") (field (name "MANUFACTURER") "Vishay-Dale"))
      (libsource (lib "Altium Vault - TI") (part "Resistor"))
    )
    (comp (ref "R77")
      (value "CRCW12065K10JNEA")
      (footprint "1206")
      (description "RES, 5.1 k, 5%, 0.25 W, AEC-Q200 Grade 0, 1206")
      (fields (field (name "VALUEDISPLAYED") "5.1k") (field (name "MANUFACTURER") "Vishay-Dale"))
      (libsource (lib "Altium Vault - TI") (part "Resistor"))
    )
    (comp (ref "R78")
      (value "Resistor")
      (footprint "0603")
      (description "RES, 1.0 k, 5%, 0.1 W, AEC-Q200 Grade 0, 0603")
      (fields
        (field (name "PARTNUMBER") "CRCW06031K00JNEA")
        (field (name "MANUFACTURER") "Vishay-Dale")
        (field (name "VALUEDISPLAYED") "1.0k")
        (field (name "PUBLISHER") "Texas Instruments")
      )
      (libsource (lib "Altium Vault - TI") (part "Resistor"))
    )
    (comp (ref "R79")
      (value "CRCW060320K0JNEA")
      (footprint "0603")
      (description "RES, 20 k, 5%, 0.1 W, AEC-Q200 Grade 0, 0603")
      (fields (field (name "MANUFACTURER") "Vishay-Dale") (field (name "VALUEDISPLAYED") "20k"))
      (libsource (lib "Altium Vault - TI") (part "Resistor"))
    )
    (comp (ref "R80")
      (value "CRCW060327K0JNEA")
      (footprint "0603")
      (description "RES, 27 k, 5%, 0.1 W, AEC-Q200 Grade 0, 0603")
      (fields (field (name "MANUFACTURER") "Vishay-Dale") (field (name "VALUEDISPLAYED") "27k"))
      (libsource (lib "Altium Vault - TI") (part "Resistor"))
    )
    (comp (ref "R81")
      (value "Resistor")
      (footprint "0603")
      (description "RES, 100, 5%, 0.1 W, AEC-Q200 Grade 0, 0603")
      (fields
        (field (name "PARTNUMBER") "CRCW0603100RJNEA")
        (field (name "MANUFACTURER") "Vishay-Dale")
        (field (name "VALUEDISPLAYED") "100")
        (field (name "PUBLISHER") "Texas Instruments")
      )
      (libsource (lib "Altium Vault - TI") (part "Resistor"))
    )
    (comp (ref "R82")
      (value "Resistor")
      (footprint "0603")
      (description "RES, 5.1 k, 5%, 0.1 W, AEC-Q200 Grade 0, 0603")
      (fields
        (field (name "PARTNUMBER") "CRCW06035K10JNEA")
        (field (name "MANUFACTURER") "Vishay-Dale")
        (field (name "VALUEDISPLAYED") "5.1k")
        (field (name "PUBLISHER") "Texas Instruments")
      )
      (libsource (lib "Altium Vault - TI") (part "Resistor"))
    )
    (comp (ref "R83")
      (value "Resistor")
      (footprint "0603")
      (description "RES, 1.0 k, 5%, 0.1 W, AEC-Q200 Grade 0, 0603")
      (fields
        (field (name "PARTNUMBER") "CRCW06031K00JNEA")
        (field (name "MANUFACTURER") "Vishay-Dale")
        (field (name "VALUEDISPLAYED") "1.0k")
        (field (name "PUBLISHER") "Texas Instruments")
      )
      (libsource (lib "Altium Vault - TI") (part "Resistor"))
    )
    (comp (ref "R84")
      (value "Resistor")
      (footprint "0603")
      (description "RES, 1.0 k, 5%, 0.1 W, AEC-Q200 Grade 0, 0603")
      (fields
        (field (name "PARTNUMBER") "CRCW06031K00JNEA")
        (field (name "MANUFACTURER") "Vishay-Dale")
        (field (name "VALUEDISPLAYED") "1.0k")
        (field (name "PUBLISHER") "Texas Instruments")
      )
      (libsource (lib "Altium Vault - TI") (part "Resistor"))
    )
    (comp (ref "R85")
      (value "Resistor")
      (footprint "0603")
      (description "RES, 1.0 k, 5%, 0.1 W, AEC-Q200 Grade 0, 0603")
      (fields
        (field (name "PARTNUMBER") "CRCW06031K00JNEA")
        (field (name "MANUFACTURER") "Vishay-Dale")
        (field (name "VALUEDISPLAYED") "1.0k")
        (field (name "PUBLISHER") "Texas Instruments")
      )
      (libsource (lib "Altium Vault - TI") (part "Resistor"))
    )
    (comp (ref "R86")
      (value "Resistor")
      (footprint "0603")
      (description "RES, 1.0 k, 5%, 0.1 W, AEC-Q200 Grade 0, 0603")
      (fields
        (field (name "PARTNUMBER") "CRCW06031K00JNEA")
        (field (name "MANUFACTURER") "Vishay-Dale")
        (field (name "VALUEDISPLAYED") "1.0k")
        (field (name "PUBLISHER") "Texas Instruments")
      )
      (libsource (lib "Altium Vault - TI") (part "Resistor"))
    )
    (comp (ref "TP20")
      (value "TESTPOINT")
      (footprint "TP_VIA_060RND040")
      (description "TEST POINT.  No entry in BOM.")
      (libsource (lib "Altium Vault - TI") (part "CMP-0078143-2"))
    )
    (comp (ref "TP21")
      (value "TESTPOINT")
      (footprint "TP_VIA_060RND040")
      (description "TEST POINT.  No entry in BOM.")
      (libsource (lib "Altium Vault - TI") (part "CMP-0078143-2"))
    )
    (comp (ref "TP22")
      (value "TESTPOINT")
      (footprint "TP_VIA_060RND040")
      (description "TEST POINT.  No entry in BOM.")
      (libsource (lib "Altium Vault - TI") (part "CMP-0078143-2"))
    )
    (comp (ref "TP23")
      (value "TESTPOINT")
      (footprint "TP_VIA_060RND040")
      (description "TEST POINT.  No entry in BOM.")
      (libsource (lib "Altium Vault - TI") (part "CMP-0078143-2"))
    )
    (comp (ref "TP24")
      (value "TESTPOINT")
      (footprint "TP_VIA_060RND040")
      (description "TEST POINT.  No entry in BOM.")
      (libsource (lib "Altium Vault - TI") (part "CMP-0078143-2"))
    )
    (comp (ref "TP25")
      (value "TESTPOINT")
      (footprint "TP_VIA_060RND040")
      (description "TEST POINT.  No entry in BOM.")
      (libsource (lib "Altium Vault - TI") (part "CMP-0078143-2"))
    )
    (comp (ref "TP26")
      (value "TESTPOINT")
      (footprint "TP_VIA_060RND040")
      (description "TEST POINT.  No entry in BOM.")
      (libsource (lib "Altium Vault - TI") (part "CMP-0078143-2"))
    )
    (comp (ref "TP27")
      (value "TESTPOINT")
      (footprint "TP_VIA_060RND040")
      (description "TEST POINT.  No entry in BOM.")
      (libsource (lib "Altium Vault - TI") (part "CMP-0078143-2"))
    )
    (comp (ref "TP28")
      (value "TESTPOINT")
      (footprint "TP_VIA_060RND040")
      (description "TEST POINT.  No entry in BOM.")
      (libsource (lib "Altium Vault - TI") (part "CMP-0078143-2"))
    )
    (comp (ref "TP29")
      (value "TESTPOINT")
      (footprint "TP_VIA_060RND040")
      (description "TEST POINT.  No entry in BOM.")
      (libsource (lib "Altium Vault - TI") (part "CMP-0078143-2"))
    )
    (comp (ref "TP30")
      (value "TESTPOINT")
      (footprint "TP_VIA_060RND040")
      (description "TEST POINT.  No entry in BOM.")
      (libsource (lib "Altium Vault - TI") (part "CMP-0078143-2"))
    )
    (comp (ref "TP31")
      (value "TESTPOINT")
      (footprint "TP_VIA_060RND040")
      (description "TEST POINT.  No entry in BOM.")
      (libsource (lib "Altium Vault - TI") (part "CMP-0078143-2"))
    )
    (comp (ref "TP32")
      (value "TESTPOINT")
      (footprint "TP_VIA_060RND040")
      (description "TEST POINT.  No entry in BOM.")
      (libsource (lib "Altium Vault - TI") (part "CMP-0078143-2"))
    )
    (comp (ref "TP33")
      (value "TESTPOINT")
      (footprint "TP_VIA_060RND040")
      (description "TEST POINT.  No entry in BOM.")
      (libsource (lib "Altium Vault - TI") (part "CMP-0078143-2"))
    )
    (comp (ref "TP34")
      (value "TESTPOINT")
      (footprint "TP_VIA_060RND040")
      (description "TEST POINT.  No entry in BOM.")
      (libsource (lib "Altium Vault - TI") (part "CMP-0078143-2"))
    )
    (comp (ref "TP35")
      (value "TESTPOINT")
      (footprint "TP_VIA_060RND040")
      (description "TEST POINT.  No entry in BOM.")
      (libsource (lib "Altium Vault - TI") (part "CMP-0078143-2"))
    )
    (comp (ref "TP36")
      (value "TESTPOINT")
      (footprint "TP_VIA_060RND040")
      (description "TEST POINT.  No entry in BOM.")
      (libsource (lib "Altium Vault - TI") (part "CMP-0078143-2"))
    )
    (comp (ref "U2")
      (value "BQ771807DPJR")
      (footprint "DPJ0008A")
      (description "Family 2-5S Overvoltage Protector with Internal Delay Timer, DPJ0008A (WSON-8)")
      (fields
        (field (name "ALTERNATE PARTNUMBER") "BQ771807DPJT")
        (field (name "MANUFACTURER") "Texas Instruments")
        (field (name "PARTNUMBER") "BQ771807DPJR")
      )
      (libsource (lib "Altium Vault - TI") (part "BQ77180x"))
    )
    (comp (ref "U3")
      (value "BQ771807DPJR")
      (footprint "DPJ0008A")
      (description "Family 2-5S Overvoltage Protector with Internal Delay Timer, DPJ0008A (WSON-8)")
      (fields
        (field (name "ALTERNATE PARTNUMBER") "BQ771807DPJT")
        (field (name "MANUFACTURER") "Texas Instruments")
        (field (name "PARTNUMBER") "BQ771807DPJR")
      )
      (libsource (lib "Altium Vault - TI") (part "BQ77180x"))
    )
    (comp (ref "U4")
      (value "BQ771807DPJR")
      (footprint "DPJ0008A")
      (description "Family 2-5S Overvoltage Protector with Internal Delay Timer, DPJ0008A (WSON-8)")
      (fields
        (field (name "ALTERNATE PARTNUMBER") "BQ771807DPJT")
        (field (name "MANUFACTURER") "Texas Instruments")
        (field (name "PARTNUMBER") "BQ771807DPJR")
      )
      (libsource (lib "Altium Vault - TI") (part "BQ77180x"))
    )
    (comp (ref "U5")
      (value "BQ771807DPJR")
      (footprint "DPJ0008A")
      (description "Family 2-5S Overvoltage Protector with Internal Delay Timer, DPJ0008A (WSON-8)")
      (fields
        (field (name "ALTERNATE PARTNUMBER") "BQ771807DPJT")
        (field (name "MANUFACTURER") "Texas Instruments")
        (field (name "PARTNUMBER") "BQ771807DPJR")
      )
      (libsource (lib "Altium Vault - TI") (part "BQ77180x"))
    )
  )
  (nets
    (net (code "1") (name "/CPACK+") (class "Default")
      (node (ref "C30") (pin "1") (pinfunction "1_1") (pintype "passive"))
      (node (ref "C34") (pin "1") (pinfunction "1_1") (pintype "passive"))
      (node (ref "E1") (pin "1") (pinfunction "1_1") (pintype "passive"))
      (node (ref "J8") (pin "1") (pinfunction "1_1") (pintype "passive"))
      (node (ref "J8") (pin "2") (pinfunction "2_2") (pintype "passive"))
      (node (ref "Q2") (pin "2") (pinfunction "S_2") (pintype "passive"))
      (node (ref "Q3") (pin "5") (pinfunction "D_5") (pintype "passive"))
      (node (ref "Q3") (pin "6") (pinfunction "D_6") (pintype "passive"))
      (node (ref "Q3") (pin "7") (pinfunction "D_7") (pintype "passive"))
      (node (ref "Q3") (pin "8") (pinfunction "D_8") (pintype "passive"))
      (node (ref "Q3") (pin "9") (pinfunction "D_9") (pintype "passive"))
      (node (ref "R35") (pin "1") (pinfunction "1_1") (pintype "passive"))
      (node (ref "R71") (pin "1") (pinfunction "1_1") (pintype "passive"))
      (node (ref "TP20") (pin "1") (pintype "passive"))
    )
    (net (code "2") (name "/FBAT") (class "Default")
      (node (ref "C29") (pin "2") (pinfunction "2_2") (pintype "passive"))
      (node (ref "C37") (pin "2") (pinfunction "2_2") (pintype "passive"))
      (node (ref "D4") (pin "2") (pinfunction "A_2") (pintype "passive"))
      (node (ref "F1") (pin "3") (pinfunction "Fuse_3") (pintype "passive"))
      (node (ref "NT2") (pin "1") (pinfunction "1_1") (pintype "passive"))
      (node (ref "Q3") (pin "1") (pinfunction "S_1") (pintype "passive"))
      (node (ref "Q3") (pin "2") (pinfunction "S_2") (pintype "passive"))
      (node (ref "Q3") (pin "3") (pinfunction "S_3") (pintype "passive"))
      (node (ref "Q8") (pin "1") (pinfunction "S_1") (pintype "passive"))
      (node (ref "Q8") (pin "2") (pinfunction "S_2") (pintype "passive"))
      (node (ref "Q8") (pin "3") (pinfunction "S_3") (pintype "passive"))
      (node (ref "R33") (pin "1") (pinfunction "1_1") (pintype "passive"))
      (node (ref "R39") (pin "1") (pinfunction "1_1") (pintype "passive"))
      (node (ref "R46") (pin "1") (pinfunction "1_1") (pintype "passive"))
      (node (ref "R50") (pin "1") (pinfunction "1_1") (pintype "passive"))
      (node (ref "TP21") (pin "1") (pintype "passive"))
    )
    (net (code "3") (name "/PACK+") (class "Default")
      (node (ref "C38") (pin "1") (pinfunction "1_1") (pintype "passive"))
      (node (ref "C42") (pin "1") (pinfunction "1_1") (pintype "passive"))
      (node (ref "D5") (pin "2") (pinfunction "A_2") (pintype "passive"))
      (node (ref "D6") (pin "2") (pinfunction "A_2") (pintype "passive"))
      (node (ref "E2") (pin "1") (pinfunction "1_1") (pintype "passive"))
      (node (ref "J9") (pin "3") (pinfunction "3_3") (pintype "passive"))
      (node (ref "J9") (pin "4") (pinfunction "4_4") (pintype "passive"))
      (node (ref "Q10") (pin "2") (pinfunction "S_2") (pintype "passive"))
      (node (ref "Q7") (pin "1") (pinfunction "S_1") (pintype "passive"))
      (node (ref "Q7") (pin "2") (pinfunction "S_2") (pintype "passive"))
      (node (ref "Q7") (pin "3") (pinfunction "S_3") (pintype "passive"))
      (node (ref "Q9") (pin "1") (pinfunction "S_1") (pintype "passive"))
      (node (ref "Q9") (pin "2") (pinfunction "S_2") (pintype "passive"))
      (node (ref "Q9") (pin "3") (pinfunction "S_3") (pintype "passive"))
      (node (ref "R40") (pin "2") (pinfunction "2_2") (pintype "passive"))
      (node (ref "R51") (pin "1") (pinfunction "1_1") (pintype "passive"))
      (node (ref "R52") (pin "1") (pinfunction "1_1") (pintype "passive"))
      (node (ref "R74") (pin "1") (pinfunction "1_1") (pintype "passive"))
      (node (ref "R77") (pin "1") (pinfunction "1_1") (pintype "passive"))
      (node (ref "TP22") (pin "1") (pintype "passive"))
    )
    (net (code "4") (name "1P") (class "Default")
      (node (ref "R86") (pin "1") (pinfunction "1_1") (pintype "passive"))
    )
    (net (code "5") (name "2P") (class "Default")
      (node (ref "R85") (pin "1") (pinfunction "1_1") (pintype "passive"))
    )
    (net (code "6") (name "3P") (class "Default")
      (node (ref "R84") (pin "1") (pinfunction "1_1") (pintype "passive"))
    )
    (net (code "7") (name "4P") (class "Default")
      (node (ref "C49") (pin "1") (pinfunction "1_1") (pintype "passive"))
      (node (ref "C52") (pin "1") (pinfunction "1_1") (pintype "passive"))
      (node (ref "R79") (pin "1") (pinfunction "1_1") (pintype "passive"))
      (node (ref "R81") (pin "1") (pinfunction "1_1") (pintype "passive"))
      (node (ref "R83") (pin "1") (pinfunction "1_1") (pintype "passive"))
      (node (ref "U4") (pin "7") (pinfunction "VSS_7") (pintype "power_in"))
      (node (ref "U4") (pin "9") (pinfunction "PAD_9") (pintype "passive"))
    )
    (net (code "8") (name "5P") (class "Default")
      (node (ref "R78") (pin "1") (pinfunction "1_1") (pintype "passive"))
    )
    (net (code "9") (name "6P") (class "Default")
      (node (ref "R75") (pin "1") (pinfunction "1_1") (pintype "passive"))
    )
    (net (code "10") (name "7P") (class "Default")
      (node (ref "R72") (pin "1") (pinfunction "1_1") (pintype "passive"))
    )
    (net (code "11") (name "8P") (class "Default")
      (node (ref "C41") (pin "1") (pinfunction "1_1") (pintype "passive"))
      (node (ref "C46") (pin "1") (pinfunction "1_1") (pintype "passive"))
      (node (ref "R58") (pin "1") (pinfunction "1_1") (pintype "passive"))
      (node (ref "R67") (pin "1") (pinfunction "1_1") (pintype "passive"))
      (node (ref "R69") (pin "1") (pinfunction "1_1") (pintype "passive"))
      (node (ref "U3") (pin "7") (pinfunction "VSS_7") (pintype "power_in"))
      (node (ref "U3") (pin "9") (pinfunction "PAD_9") (pintype "passive"))
    )
    (net (code "12") (name "9P") (class "Default")
      (node (ref "R54") (pin "1") (pinfunction "1_1") (pintype "passive"))
    )
    (net (code "13") (name "10P") (class "Default")
      (node (ref "R53") (pin "1") (pinfunction "1_1") (pintype "passive"))
    )
    (net (code "14") (name "11P") (class "Default")
      (node (ref "R49") (pin "1") (pinfunction "1_1") (pintype "passive"))
    )
    (net (code "15") (name "12P") (class "Default")
      (node (ref "C32") (pin "1") (pinfunction "1_1") (pintype "passive"))
      (node (ref "C39") (pin "1") (pinfunction "1_1") (pintype "passive"))
      (node (ref "R38") (pin "1") (pinfunction "1_1") (pintype "passive"))
      (node (ref "R41") (pin "1") (pinfunction "1_1") (pintype "passive"))
      (node (ref "R47") (pin "1") (pinfunction "1_1") (pintype "passive"))
      (node (ref "U2") (pin "7") (pinfunction "VSS_7") (pintype "power_in"))
      (node (ref "U2") (pin "9") (pinfunction "PAD_9") (pintype "passive"))
    )
    (net (code "16") (name "13P") (class "Default")
      (node (ref "R37") (pin "1") (pinfunction "1_1") (pintype "passive"))
    )
    (net (code "17") (name "14P") (class "Default")
      (node (ref "R36") (pin "1") (pinfunction "1_1") (pintype "passive"))
    )
    (net (code "18") (name "15P") (class "Default")
      (node (ref "R34") (pin "1") (pinfunction "1_1") (pintype "passive"))
    )
    (net (code "19") (name "16P") (class "Default")
      (node (ref "D3") (pin "2") (pinfunction "A_2") (pintype "passive"))
      (node (ref "F1") (pin "1") (pinfunction "Fuse_1") (pintype "passive"))
      (node (ref "NT2") (pin "2") (pinfunction "2_2") (pintype "passive"))
      (node (ref "R31") (pin "1") (pinfunction "1_1") (pintype "passive"))
      (node (ref "R32") (pin "1") (pinfunction "1_1") (pintype "passive"))
    )
    (net (code "20") (name "CD") (class "Default")
      (node (ref "Q5") (pin "2") (pinfunction "S_2") (pintype "passive"))
      (node (ref "Q6") (pin "2") (pinfunction "S_2") (pintype "passive"))
      (node (ref "Q7") (pin "5") (pinfunction "D_5") (pintype "passive"))
      (node (ref "Q7") (pin "6") (pinfunction "D_6") (pintype "passive"))
      (node (ref "Q7") (pin "7") (pinfunction "D_7") (pintype "passive"))
      (node (ref "Q7") (pin "8") (pinfunction "D_8") (pintype "passive"))
      (node (ref "Q7") (pin "9") (pinfunction "D_9") (pintype "passive"))
      (node (ref "Q8") (pin "5") (pinfunction "D_5") (pintype "passive"))
      (node (ref "Q8") (pin "6") (pinfunction "D_6") (pintype "passive"))
      (node (ref "Q8") (pin "7") (pinfunction "D_7") (pintype "passive"))
      (node (ref "Q8") (pin "8") (pinfunction "D_8") (pintype "passive"))
      (node (ref "Q8") (pin "9") (pinfunction "D_9") (pintype "passive"))
      (node (ref "Q9") (pin "5") (pinfunction "D_5") (pintype "passive"))
      (node (ref "Q9") (pin "6") (pinfunction "D_6") (pintype "passive"))
      (node (ref "Q9") (pin "7") (pinfunction "D_7") (pintype "passive"))
      (node (ref "Q9") (pin "8") (pinfunction "D_8") (pintype "passive"))
      (node (ref "Q9") (pin "9") (pinfunction "D_9") (pintype "passive"))
      (node (ref "R42") (pin "1") (pinfunction "1_1") (pintype "passive"))
      (node (ref "R43") (pin "1") (pinfunction "1_1") (pintype "passive"))
      (node (ref "R46") (pin "2") (pinfunction "2_2") (pintype "passive"))
      (node (ref "TP23") (pin "1") (pintype "passive"))
    )
    (net (code "21") (name "CHG") (class "Default")
      (node (ref "R61") (pin "1") (pinfunction "1_1") (pintype "passive"))
      (node (ref "TP30") (pin "1") (pintype "passive"))
    )
    (net (code "22") (name "DSG") (class "Default")
      (node (ref "D10") (pin "1") (pinfunction "K_1") (pintype "passive"))
      (node (ref "D9") (pin "1") (pinfunction "K_1") (pintype "passive"))
      (node (ref "R68") (pin "1") (pinfunction "1_1") (pintype "passive"))
      (node (ref "TP35") (pin "1") (pintype "passive"))
    )
    (net (code "23") (name "FUSE") (class "Default")
      (node (ref "R59") (pin "2") (pinfunction "2_2") (pintype "passive"))
    )
    (net (code "24") (name "LD") (class "Default")
      (node (ref "D12") (pin "1") (pinfunction "K_1") (pintype "passive"))
      (node (ref "R76") (pin "2") (pinfunction "2_2") (pintype "passive"))
      (node (ref "TP34") (pin "1") (pintype "passive"))
    )
    (net (code "25") (name "Net-(C29-Pad1)") (class "Default")
      (node (ref "C29") (pin "1") (pinfunction "1_1") (pintype "passive"))
      (node (ref "C30") (pin "2") (pinfunction "2_2") (pintype "passive"))
    )
    (net (code "26") (name "Net-(C34-Pad2)") (class "Default")
      (node (ref "C34") (pin "2") (pinfunction "2_2") (pintype "passive"))
      (node (ref "C36") (pin "1") (pinfunction "1_1") (pintype "passive"))
    )
    (net (code "27") (name "Net-(C37-Pad1)") (class "Default")
      (node (ref "C37") (pin "1") (pinfunction "1_1") (pintype "passive"))
      (node (ref "C38") (pin "2") (pinfunction "2_2") (pintype "passive"))
    )
    (net (code "28") (name "Net-(C42-Pad2)") (class "Default")
      (node (ref "C42") (pin "2") (pinfunction "2_2") (pintype "passive"))
      (node (ref "C45") (pin "1") (pinfunction "1_1") (pintype "passive"))
    )
    (net (code "29") (name "Net-(D3-K)") (class "Default")
      (node (ref "D3") (pin "1") (pinfunction "K_1") (pintype "passive"))
      (node (ref "R45") (pin "2") (pinfunction "2_2") (pintype "passive"))
    )
    (net (code "30") (name "Net-(D4-K)") (class "Default")
      (node (ref "D4") (pin "1") (pinfunction "K_1") (pintype "passive"))
      (node (ref "Q3") (pin "4") (pinfunction "G_4") (pintype "passive"))
      (node (ref "Q8") (pin "4") (pinfunction "G_4") (pintype "passive"))
      (node (ref "R50") (pin "2") (pinfunction "2_2") (pintype "passive"))
      (node (ref "R61") (pin "2") (pinfunction "2_2") (pintype "passive"))
      (node (ref "TP25") (pin "1") (pintype "passive"))
    )
    (net (code "31") (name "Net-(D5-K)") (class "Default")
      (node (ref "D5") (pin "1") (pinfunction "K_1") (pintype "passive"))
      (node (ref "Q10") (pin "3") (pinfunction "D_3") (pintype "passive"))
      (node (ref "R51") (pin "2") (pinfunction "2_2") (pintype "passive"))
      (node (ref "R55") (pin "2") (pinfunction "2_2") (pintype "passive"))
      (node (ref "R56") (pin "2") (pinfunction "2_2") (pintype "passive"))
      (node (ref "R64") (pin "2") (pinfunction "2_2") (pintype "passive"))
      (node (ref "R65") (pin "2") (pinfunction "2_2") (pintype "passive"))
      (node (ref "TP28") (pin "1") (pintype "passive"))
    )
    (net (code "32") (name "Net-(D6-K)") (class "Default")
      (node (ref "D6") (pin "1") (pinfunction "K_1") (pintype "passive"))
      (node (ref "Q10") (pin "1") (pinfunction "G_1") (pintype "passive"))
      (node (ref "R52") (pin "2") (pinfunction "2_2") (pintype "passive"))
      (node (ref "R57") (pin "1") (pinfunction "1_1") (pintype "passive"))
    )
    (net (code "33") (name "Net-(D7-K)") (class "Default")
      (node (ref "D7") (pin "1") (pinfunction "K_1") (pintype "passive"))
      (node (ref "R57") (pin "2") (pinfunction "2_2") (pintype "passive"))
    )
    (net (code "34") (name "Net-(D9-A)") (class "Default")
      (node (ref "D9") (pin "2") (pinfunction "A_2") (pintype "passive"))
      (node (ref "R65") (pin "1") (pinfunction "1_1") (pintype "passive"))
    )
    (net (code "35") (name "Net-(D13-A)") (class "Default")
      (node (ref "D13") (pin "1") (pinfunction "A_1") (pintype "passive"))
      (node (ref "R82") (pin "2") (pinfunction "2_2") (pintype "passive"))
    )
    (net (code "36") (name "Net-(D13-K)") (class "Default")
      (node (ref "C47") (pin "2") (pinfunction "2_2") (pintype "passive"))
      (node (ref "D13") (pin "3") (pinfunction "K_3") (pintype "passive"))
      (node (ref "D8") (pin "1") (pinfunction "K_1") (pintype "passive"))
      (node (ref "Q12") (pin "4") (pinfunction "G_4") (pintype "passive"))
      (node (ref "R44") (pin "2") (pinfunction "2_2") (pintype "passive"))
      (node (ref "R59") (pin "1") (pinfunction "1_1") (pintype "passive"))
      (node (ref "R60") (pin "2") (pinfunction "2_2") (pintype "passive"))
      (node (ref "R66") (pin "2") (pinfunction "2_2") (pintype "passive"))
      (node (ref "R80") (pin "2") (pinfunction "2_2") (pintype "passive"))
      (node (ref "TP29") (pin "1") (pintype "passive"))
    )
    (net (code "37") (name "Net-(F1-Heater)") (class "Default")
      (node (ref "F1") (pin "2") (pinfunction "Heater_2") (pintype "passive"))
      (node (ref "Q12") (pin "5") (pinfunction "D_5") (pintype "passive"))
      (node (ref "Q12") (pin "6") (pinfunction "D_6") (pintype "passive"))
      (node (ref "Q12") (pin "7") (pinfunction "D_7") (pintype "passive"))
      (node (ref "Q12") (pin "8") (pinfunction "D_8") (pintype "passive"))
      (node (ref "Q12") (pin "9") (pinfunction "D_9") (pintype "passive"))
      (node (ref "R48") (pin "1") (pinfunction "1_1") (pintype "passive"))
      (node (ref "TP24") (pin "1") (pintype "passive"))
    )
    (net (code "38") (name "Net-(Q2-D)") (class "Default")
      (node (ref "Q2") (pin "3") (pinfunction "D_3") (pintype "passive"))
      (node (ref "R33") (pin "2") (pinfunction "2_2") (pintype "passive"))
    )
    (net (code "39") (name "Net-(Q2-G)") (class "Default")
      (node (ref "Q2") (pin "1") (pinfunction "G_1") (pintype "passive"))
      (node (ref "Q5") (pin "1") (pinfunction "G_1") (pintype "passive"))
      (node (ref "R35") (pin "2") (pinfunction "2_2") (pintype "passive"))
      (node (ref "R43") (pin "2") (pinfunction "2_2") (pintype "passive"))
      (node (ref "R62") (pin "2") (pinfunction "2_2") (pintype "passive"))
      (node (ref "TP26") (pin "1") (pintype "passive"))
    )
    (net (code "40") (name "Net-(Q4-B)") (class "Default")
      (node (ref "Q4") (pin "1") (pinfunction "B_1") (pintype "passive"))
      (node (ref "R38") (pin "2") (pinfunction "2_2") (pintype "passive"))
    )
    (net (code "41") (name "Net-(Q4-C)") (class "Default")
      (node (ref "Q4") (pin "3") (pinfunction "C_3") (pintype "passive"))
      (node (ref "R44") (pin "1") (pinfunction "1_1") (pintype "passive"))
    )
    (net (code "42") (name "Net-(Q4-E)") (class "Default")
      (node (ref "Q4") (pin "2") (pinfunction "E_2") (pintype "passive"))
      (node (ref "U2") (pin "8") (pinfunction "OUT_8") (pintype "output"))
    )
    (net (code "43") (name "Net-(Q5-D)") (class "Default")
      (node (ref "Q5") (pin "3") (pinfunction "D_3") (pintype "passive"))
      (node (ref "R39") (pin "2") (pinfunction "2_2") (pintype "passive"))
    )
    (net (code "44") (name "Net-(Q6-D)") (class "Default")
      (node (ref "Q6") (pin "3") (pinfunction "D_3") (pintype "passive"))
      (node (ref "R40") (pin "1") (pinfunction "1_1") (pintype "passive"))
    )
    (net (code "45") (name "Net-(Q6-G)") (class "Default")
      (node (ref "Q6") (pin "1") (pinfunction "G_1") (pintype "passive"))
      (node (ref "R42") (pin "2") (pinfunction "2_2") (pintype "passive"))
      (node (ref "R63") (pin "2") (pinfunction "2_2") (pintype "passive"))
      (node (ref "TP27") (pin "1") (pintype "passive"))
    )
    (net (code "46") (name "Net-(Q7-G)") (class "Default")
      (node (ref "Q7") (pin "4") (pinfunction "G_4") (pintype "passive"))
      (node (ref "R55") (pin "1") (pinfunction "1_1") (pintype "passive"))
    )
    (net (code "47") (name "Net-(Q9-G)") (class "Default")
      (node (ref "Q9") (pin "4") (pinfunction "G_4") (pintype "passive"))
      (node (ref "R56") (pin "1") (pinfunction "1_1") (pintype "passive"))
    )
    (net (code "48") (name "Net-(Q11-B)") (class "Default")
      (node (ref "Q11") (pin "1") (pinfunction "B_1") (pintype "passive"))
      (node (ref "R58") (pin "2") (pinfunction "2_2") (pintype "passive"))
    )
    (net (code "49") (name "Net-(Q11-C)") (class "Default")
      (node (ref "Q11") (pin "3") (pinfunction "C_3") (pintype "passive"))
      (node (ref "R60") (pin "1") (pinfunction "1_1") (pintype "passive"))
    )
    (net (code "50") (name "Net-(Q11-E)") (class "Default")
      (node (ref "Q11") (pin "2") (pinfunction "E_2") (pintype "passive"))
      (node (ref "U3") (pin "8") (pinfunction "OUT_8") (pintype "output"))
    )
    (net (code "51") (name "Net-(Q13-B)") (class "Default")
      (node (ref "Q13") (pin "1") (pinfunction "B_1") (pintype "passive"))
      (node (ref "R79") (pin "2") (pinfunction "2_2") (pintype "passive"))
    )
    (net (code "52") (name "Net-(Q13-C)") (class "Default")
      (node (ref "Q13") (pin "3") (pinfunction "C_3") (pintype "passive"))
      (node (ref "R80") (pin "1") (pinfunction "1_1") (pintype "passive"))
    )
    (net (code "53") (name "Net-(Q13-E)") (class "Default")
      (node (ref "Q13") (pin "2") (pinfunction "E_2") (pintype "passive"))
      (node (ref "U4") (pin "8") (pinfunction "OUT_8") (pintype "output"))
    )
    (net (code "54") (name "Net-(R45-Pad1)") (class "Default")
      (node (ref "R45") (pin "1") (pinfunction "1_1") (pintype "passive"))
      (node (ref "R48") (pin "2") (pinfunction "2_2") (pintype "passive"))
    )
    (net (code "55") (name "Net-(R64-Pad1)") (class "Default")
      (node (ref "R64") (pin "1") (pinfunction "1_1") (pintype "passive"))
      (node (ref "R68") (pin "2") (pinfunction "2_2") (pintype "passive"))
    )
    (net (code "56") (name "Net-(R70-Pad1)") (class "Default")
      (node (ref "R70") (pin "1") (pinfunction "1_1") (pintype "passive"))
      (node (ref "R71") (pin "2") (pinfunction "2_2") (pintype "passive"))
    )
    (net (code "57") (name "Net-(R73-Pad1)") (class "Default")
      (node (ref "R73") (pin "1") (pinfunction "1_1") (pintype "passive"))
      (node (ref "R74") (pin "2") (pinfunction "2_2") (pintype "passive"))
    )
    (net (code "58") (name "Net-(R76-Pad1)") (class "Default")
      (node (ref "R76") (pin "1") (pinfunction "1_1") (pintype "passive"))
      (node (ref "R77") (pin "2") (pinfunction "2_2") (pintype "passive"))
    )
    (net (code "59") (name "Net-(U2-V1)") (class "Default")
      (node (ref "C35") (pin "1") (pinfunction "1_1") (pintype "passive"))
      (node (ref "C39") (pin "2") (pinfunction "2_2") (pintype "passive"))
      (node (ref "R37") (pin "2") (pinfunction "2_2") (pintype "passive"))
      (node (ref "U2") (pin "6") (pinfunction "V1_6") (pintype "input"))
    )
    (net (code "60") (name "Net-(U2-V2)") (class "Default")
      (node (ref "C33") (pin "1") (pinfunction "1_1") (pintype "passive"))
      (node (ref "C35") (pin "2") (pinfunction "2_2") (pintype "passive"))
      (node (ref "R36") (pin "2") (pinfunction "2_2") (pintype "passive"))
      (node (ref "U2") (pin "5") (pinfunction "V2_5") (pintype "input"))
    )
    (net (code "61") (name "Net-(U2-V3)") (class "Default")
      (node (ref "C31") (pin "1") (pinfunction "1_1") (pintype "passive"))
      (node (ref "C33") (pin "2") (pinfunction "2_2") (pintype "passive"))
      (node (ref "R34") (pin "2") (pinfunction "2_2") (pintype "passive"))
      (node (ref "U2") (pin "4") (pinfunction "V3_4") (pintype "input"))
    )
    (net (code "62") (name "Net-(U2-V4)") (class "Default")
      (node (ref "C31") (pin "2") (pinfunction "2_2") (pintype "passive"))
      (node (ref "R32") (pin "2") (pinfunction "2_2") (pintype "passive"))
      (node (ref "U2") (pin "2") (pinfunction "V5_2") (pintype "input"))
      (node (ref "U2") (pin "3") (pinfunction "V4_3") (pintype "input"))
    )
    (net (code "63") (name "Net-(U2-VDD)") (class "Default")
      (node (ref "C32") (pin "2") (pinfunction "2_2") (pintype "passive"))
      (node (ref "R31") (pin "2") (pinfunction "2_2") (pintype "passive"))
      (node (ref "U2") (pin "1") (pinfunction "VDD_1") (pintype "power_in"))
    )
    (net (code "64") (name "Net-(U3-V1)") (class "Default")
      (node (ref "C44") (pin "1") (pinfunction "1_1") (pintype "passive"))
      (node (ref "C46") (pin "2") (pinfunction "2_2") (pintype "passive"))
      (node (ref "R54") (pin "2") (pinfunction "2_2") (pintype "passive"))
      (node (ref "U3") (pin "6") (pinfunction "V1_6") (pintype "input"))
    )
    (net (code "65") (name "Net-(U3-V2)") (class "Default")
      (node (ref "C43") (pin "1") (pinfunction "1_1") (pintype "passive"))
      (node (ref "C44") (pin "2") (pinfunction "2_2") (pintype "passive"))
      (node (ref "R53") (pin "2") (pinfunction "2_2") (pintype "passive"))
      (node (ref "U3") (pin "5") (pinfunction "V2_5") (pintype "input"))
    )
    (net (code "66") (name "Net-(U3-V3)") (class "Default")
      (node (ref "C40") (pin "1") (pinfunction "1_1") (pintype "passive"))
      (node (ref "C43") (pin "2") (pinfunction "2_2") (pintype "passive"))
      (node (ref "R49") (pin "2") (pinfunction "2_2") (pintype "passive"))
      (node (ref "U3") (pin "4") (pinfunction "V3_4") (pintype "input"))
    )
    (net (code "67") (name "Net-(U3-V4)") (class "Default")
      (node (ref "C40") (pin "2") (pinfunction "2_2") (pintype "passive"))
      (node (ref "R47") (pin "2") (pinfunction "2_2") (pintype "passive"))
      (node (ref "U3") (pin "2") (pinfunction "V5_2") (pintype "input"))
      (node (ref "U3") (pin "3") (pinfunction "V4_3") (pintype "input"))
    )
    (net (code "68") (name "Net-(U3-VDD)") (class "Default")
      (node (ref "C41") (pin "2") (pinfunction "2_2") (pintype "passive"))
      (node (ref "R41") (pin "2") (pinfunction "2_2") (pintype "passive"))
      (node (ref "U3") (pin "1") (pinfunction "VDD_1") (pintype "power_in"))
    )
    (net (code "69") (name "Net-(U4-V1)") (class "Default")
      (node (ref "C51") (pin "1") (pinfunction "1_1") (pintype "passive"))
      (node (ref "C52") (pin "2") (pinfunction "2_2") (pintype "passive"))
      (node (ref "R78") (pin "2") (pinfunction "2_2") (pintype "passive"))
      (node (ref "U4") (pin "6") (pinfunction "V1_6") (pintype "input"))
    )
    (net (code "70") (name "Net-(U4-V2)") (class "Default")
      (node (ref "C50") (pin "1") (pinfunction "1_1") (pintype "passive"))
      (node (ref "C51") (pin "2") (pinfunction "2_2") (pintype "passive"))
      (node (ref "R75") (pin "2") (pinfunction "2_2") (pintype "passive"))
      (node (ref "U4") (pin "5") (pinfunction "V2_5") (pintype "input"))
    )
    (net (code "71") (name "Net-(U4-V3)") (class "Default")
      (node (ref "C48") (pin "1") (pinfunction "1_1") (pintype "passive"))
      (node (ref "C50") (pin "2") (pinfunction "2_2") (pintype "passive"))
      (node (ref "R72") (pin "2") (pinfunction "2_2") (pintype "passive"))
      (node (ref "U4") (pin "4") (pinfunction "V3_4") (pintype "input"))
    )
    (net (code "72") (name "Net-(U4-V4)") (class "Default")
      (node (ref "C48") (pin "2") (pinfunction "2_2") (pintype "passive"))
      (node (ref "R69") (pin "2") (pinfunction "2_2") (pintype "passive"))
      (node (ref "U4") (pin "2") (pinfunction "V5_2") (pintype "input"))
      (node (ref "U4") (pin "3") (pinfunction "V4_3") (pintype "input"))
    )
    (net (code "73") (name "Net-(U4-VDD)") (class "Default")
      (node (ref "C49") (pin "2") (pinfunction "2_2") (pintype "passive"))
      (node (ref "R67") (pin "2") (pinfunction "2_2") (pintype "passive"))
      (node (ref "U4") (pin "1") (pinfunction "VDD_1") (pintype "power_in"))
    )
    (net (code "74") (name "Net-(U5-OUT)") (class "Default")
      (node (ref "R82") (pin "1") (pinfunction "1_1") (pintype "passive"))
      (node (ref "U5") (pin "8") (pinfunction "OUT_8") (pintype "output"))
    )
    (net (code "75") (name "Net-(U5-V1)") (class "Default")
      (node (ref "C56") (pin "1") (pinfunction "1_1") (pintype "passive"))
      (node (ref "C57") (pin "2") (pinfunction "2_2") (pintype "passive"))
      (node (ref "R86") (pin "2") (pinfunction "2_2") (pintype "passive"))
      (node (ref "U5") (pin "6") (pinfunction "V1_6") (pintype "input"))
    )
    (net (code "76") (name "Net-(U5-V2)") (class "Default")
      (node (ref "C55") (pin "1") (pinfunction "1_1") (pintype "passive"))
      (node (ref "C56") (pin "2") (pinfunction "2_2") (pintype "passive"))
      (node (ref "R85") (pin "2") (pinfunction "2_2") (pintype "passive"))
      (node (ref "U5") (pin "5") (pinfunction "V2_5") (pintype "input"))
    )
    (net (code "77") (name "Net-(U5-V3)") (class "Default")
      (node (ref "C53") (pin "1") (pinfunction "1_1") (pintype "passive"))
      (node (ref "C55") (pin "2") (pinfunction "2_2") (pintype "passive"))
      (node (ref "R84") (pin "2") (pinfunction "2_2") (pintype "passive"))
      (node (ref "U5") (pin "4") (pinfunction "V3_4") (pintype "input"))
    )
    (net (code "78") (name "Net-(U5-V4)") (class "Default")
      (node (ref "C53") (pin "2") (pinfunction "2_2") (pintype "passive"))
      (node (ref "R83") (pin "2") (pinfunction "2_2") (pintype "passive"))
      (node (ref "U5") (pin "2") (pinfunction "V5_2") (pintype "input"))
      (node (ref "U5") (pin "3") (pinfunction "V4_3") (pintype "input"))
    )
    (net (code "79") (name "Net-(U5-VDD)") (class "Default")
      (node (ref "C54") (pin "2") (pinfunction "2_2") (pintype "passive"))
      (node (ref "R81") (pin "2") (pinfunction "2_2") (pintype "passive"))
      (node (ref "U5") (pin "1") (pinfunction "VDD_1") (pintype "power_in"))
    )
    (net (code "80") (name "PACK") (class "Default")
      (node (ref "D11") (pin "1") (pinfunction "K_1") (pintype "passive"))
      (node (ref "R70") (pin "2") (pinfunction "2_2") (pintype "passive"))
      (node (ref "R73") (pin "2") (pinfunction "2_2") (pintype "passive"))
      (node (ref "TP33") (pin "1") (pintype "passive"))
    )
    (net (code "81") (name "PCHG") (class "Default")
      (node (ref "R62") (pin "1") (pinfunction "1_1") (pintype "passive"))
      (node (ref "TP31") (pin "1") (pintype "passive"))
    )
    (net (code "82") (name "PDSG") (class "Default")
      (node (ref "R63") (pin "1") (pinfunction "1_1") (pintype "passive"))
      (node (ref "TP32") (pin "1") (pintype "passive"))
    )
    (net (code "83") (name "PGND") (class "Default")
      (node (ref "C36") (pin "2") (pinfunction "2_2") (pintype "passive"))
      (node (ref "C45") (pin "2") (pinfunction "2_2") (pintype "passive"))
      (node (ref "D7") (pin "2") (pinfunction "A_2") (pintype "passive"))
      (node (ref "E1") (pin "2") (pinfunction "2_2") (pintype "passive"))
      (node (ref "E2") (pin "2") (pinfunction "2_2") (pintype "passive"))
      (node (ref "J9") (pin "1") (pinfunction "1_1") (pintype "passive"))
      (node (ref "J9") (pin "2") (pinfunction "2_2") (pintype "passive"))
      (node (ref "TP36") (pin "1") (pintype "passive"))
    )
    (net (code "84") (name "VSS") (class "Default")
      (node (ref "C47") (pin "1") (pinfunction "1_1") (pintype "passive"))
      (node (ref "C54") (pin "1") (pinfunction "1_1") (pintype "passive"))
      (node (ref "C57") (pin "1") (pinfunction "1_1") (pintype "passive"))
      (node (ref "D10") (pin "2") (pinfunction "A_2") (pintype "passive"))
      (node (ref "D11") (pin "2") (pinfunction "A_2") (pintype "passive"))
      (node (ref "D12") (pin "2") (pinfunction "A_2") (pintype "passive"))
      (node (ref "D8") (pin "2") (pinfunction "A_2") (pintype "passive"))
      (node (ref "Q12") (pin "1") (pinfunction "S_1") (pintype "passive"))
      (node (ref "Q12") (pin "2") (pinfunction "S_2") (pintype "passive"))
      (node (ref "Q12") (pin "3") (pinfunction "S_3") (pintype "passive"))
      (node (ref "R66") (pin "1") (pinfunction "1_1") (pintype "passive"))
      (node (ref "U5") (pin "7") (pinfunction "VSS_7") (pintype "power_in"))
      (node (ref "U5") (pin "9") (pinfunction "PAD_9") (pintype "passive"))
    )
  )
)
